# draft10_tofab.net
KiCad netlist of a schematic drawn in EAGLE
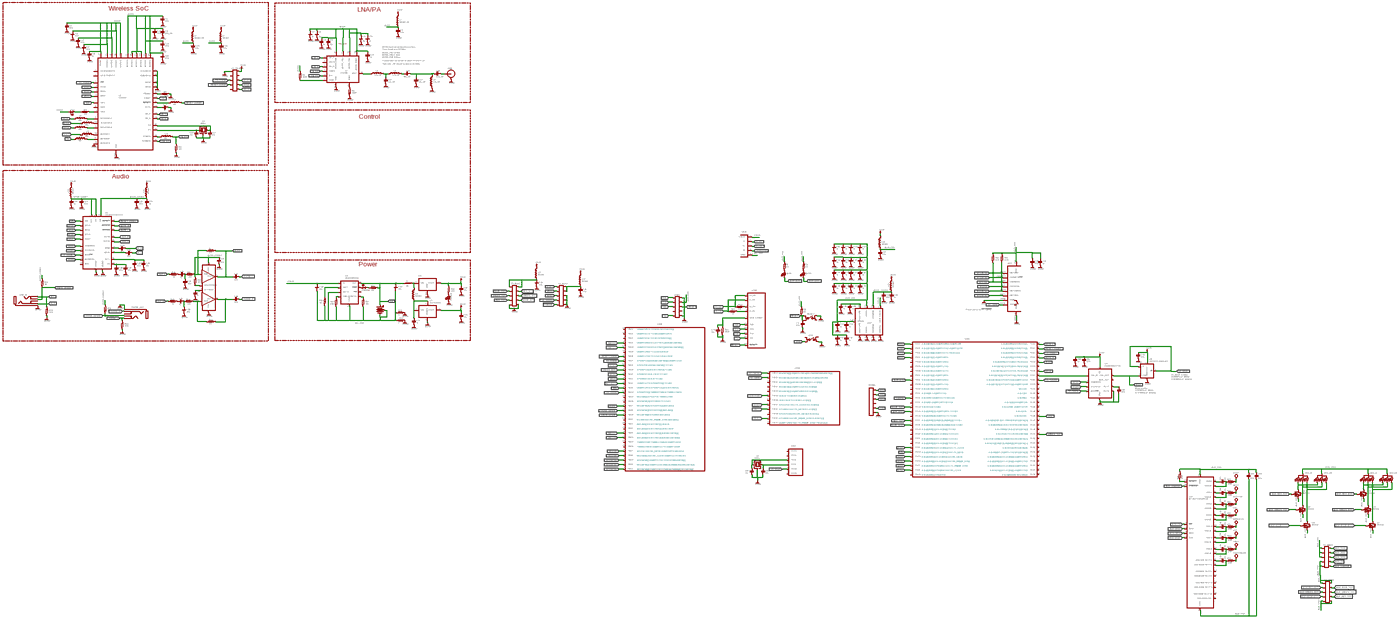
[diagram p0: schematic, sheet 1, overview]
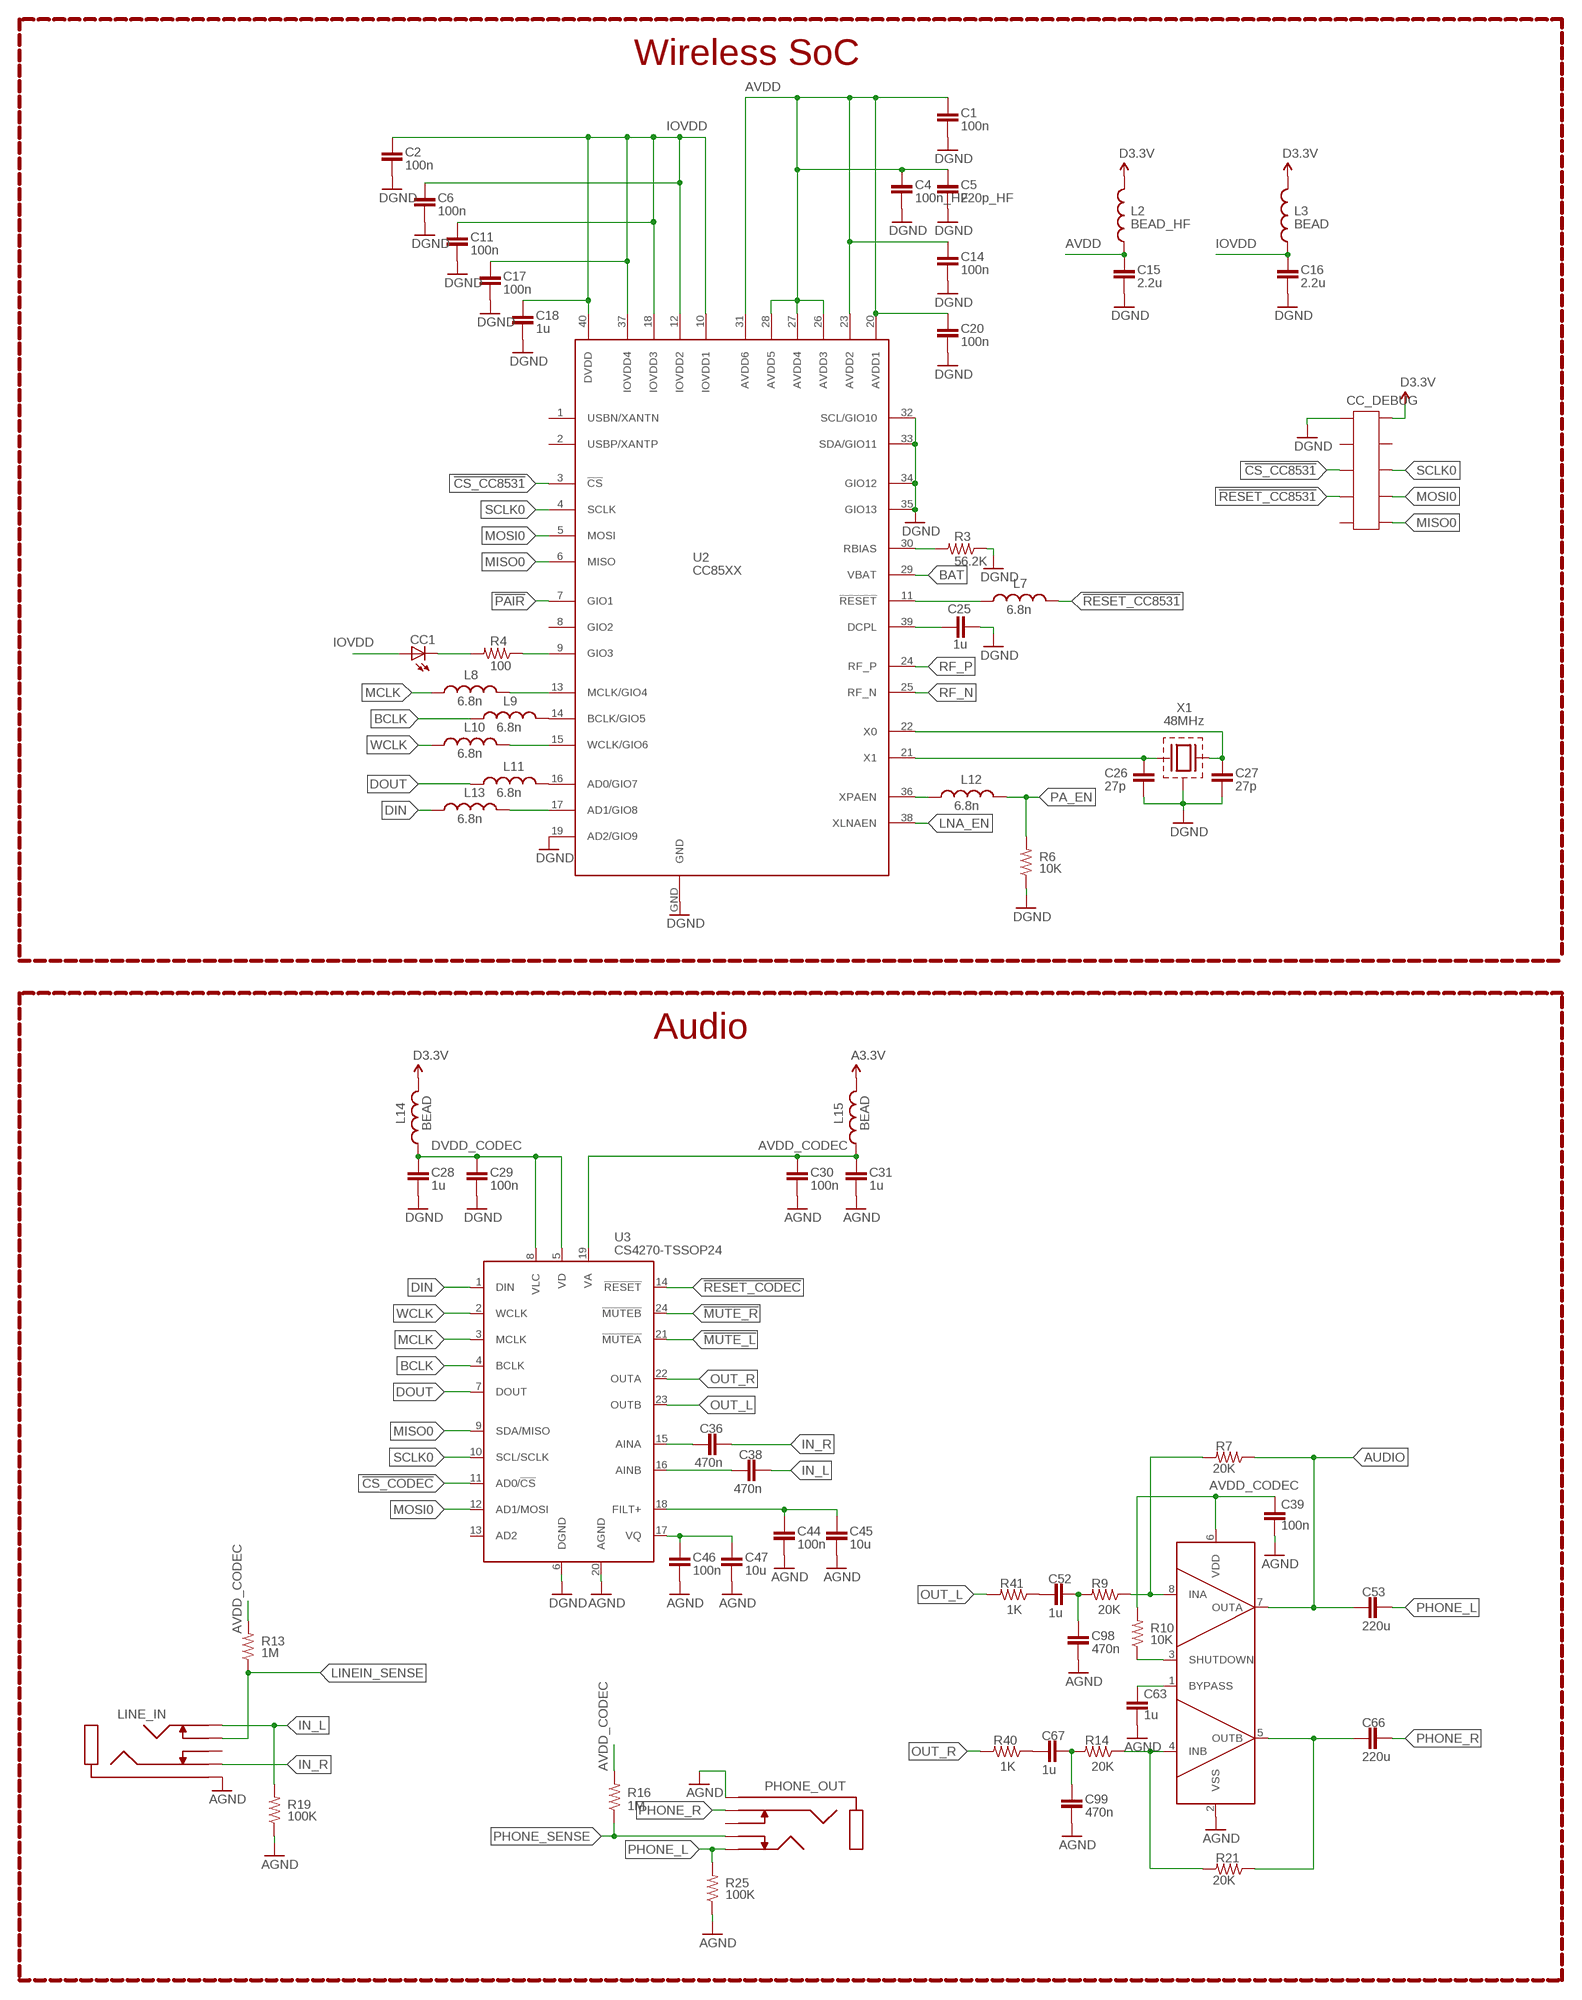
[diagram p1: schematic, sheet 1, part 1 of 4]
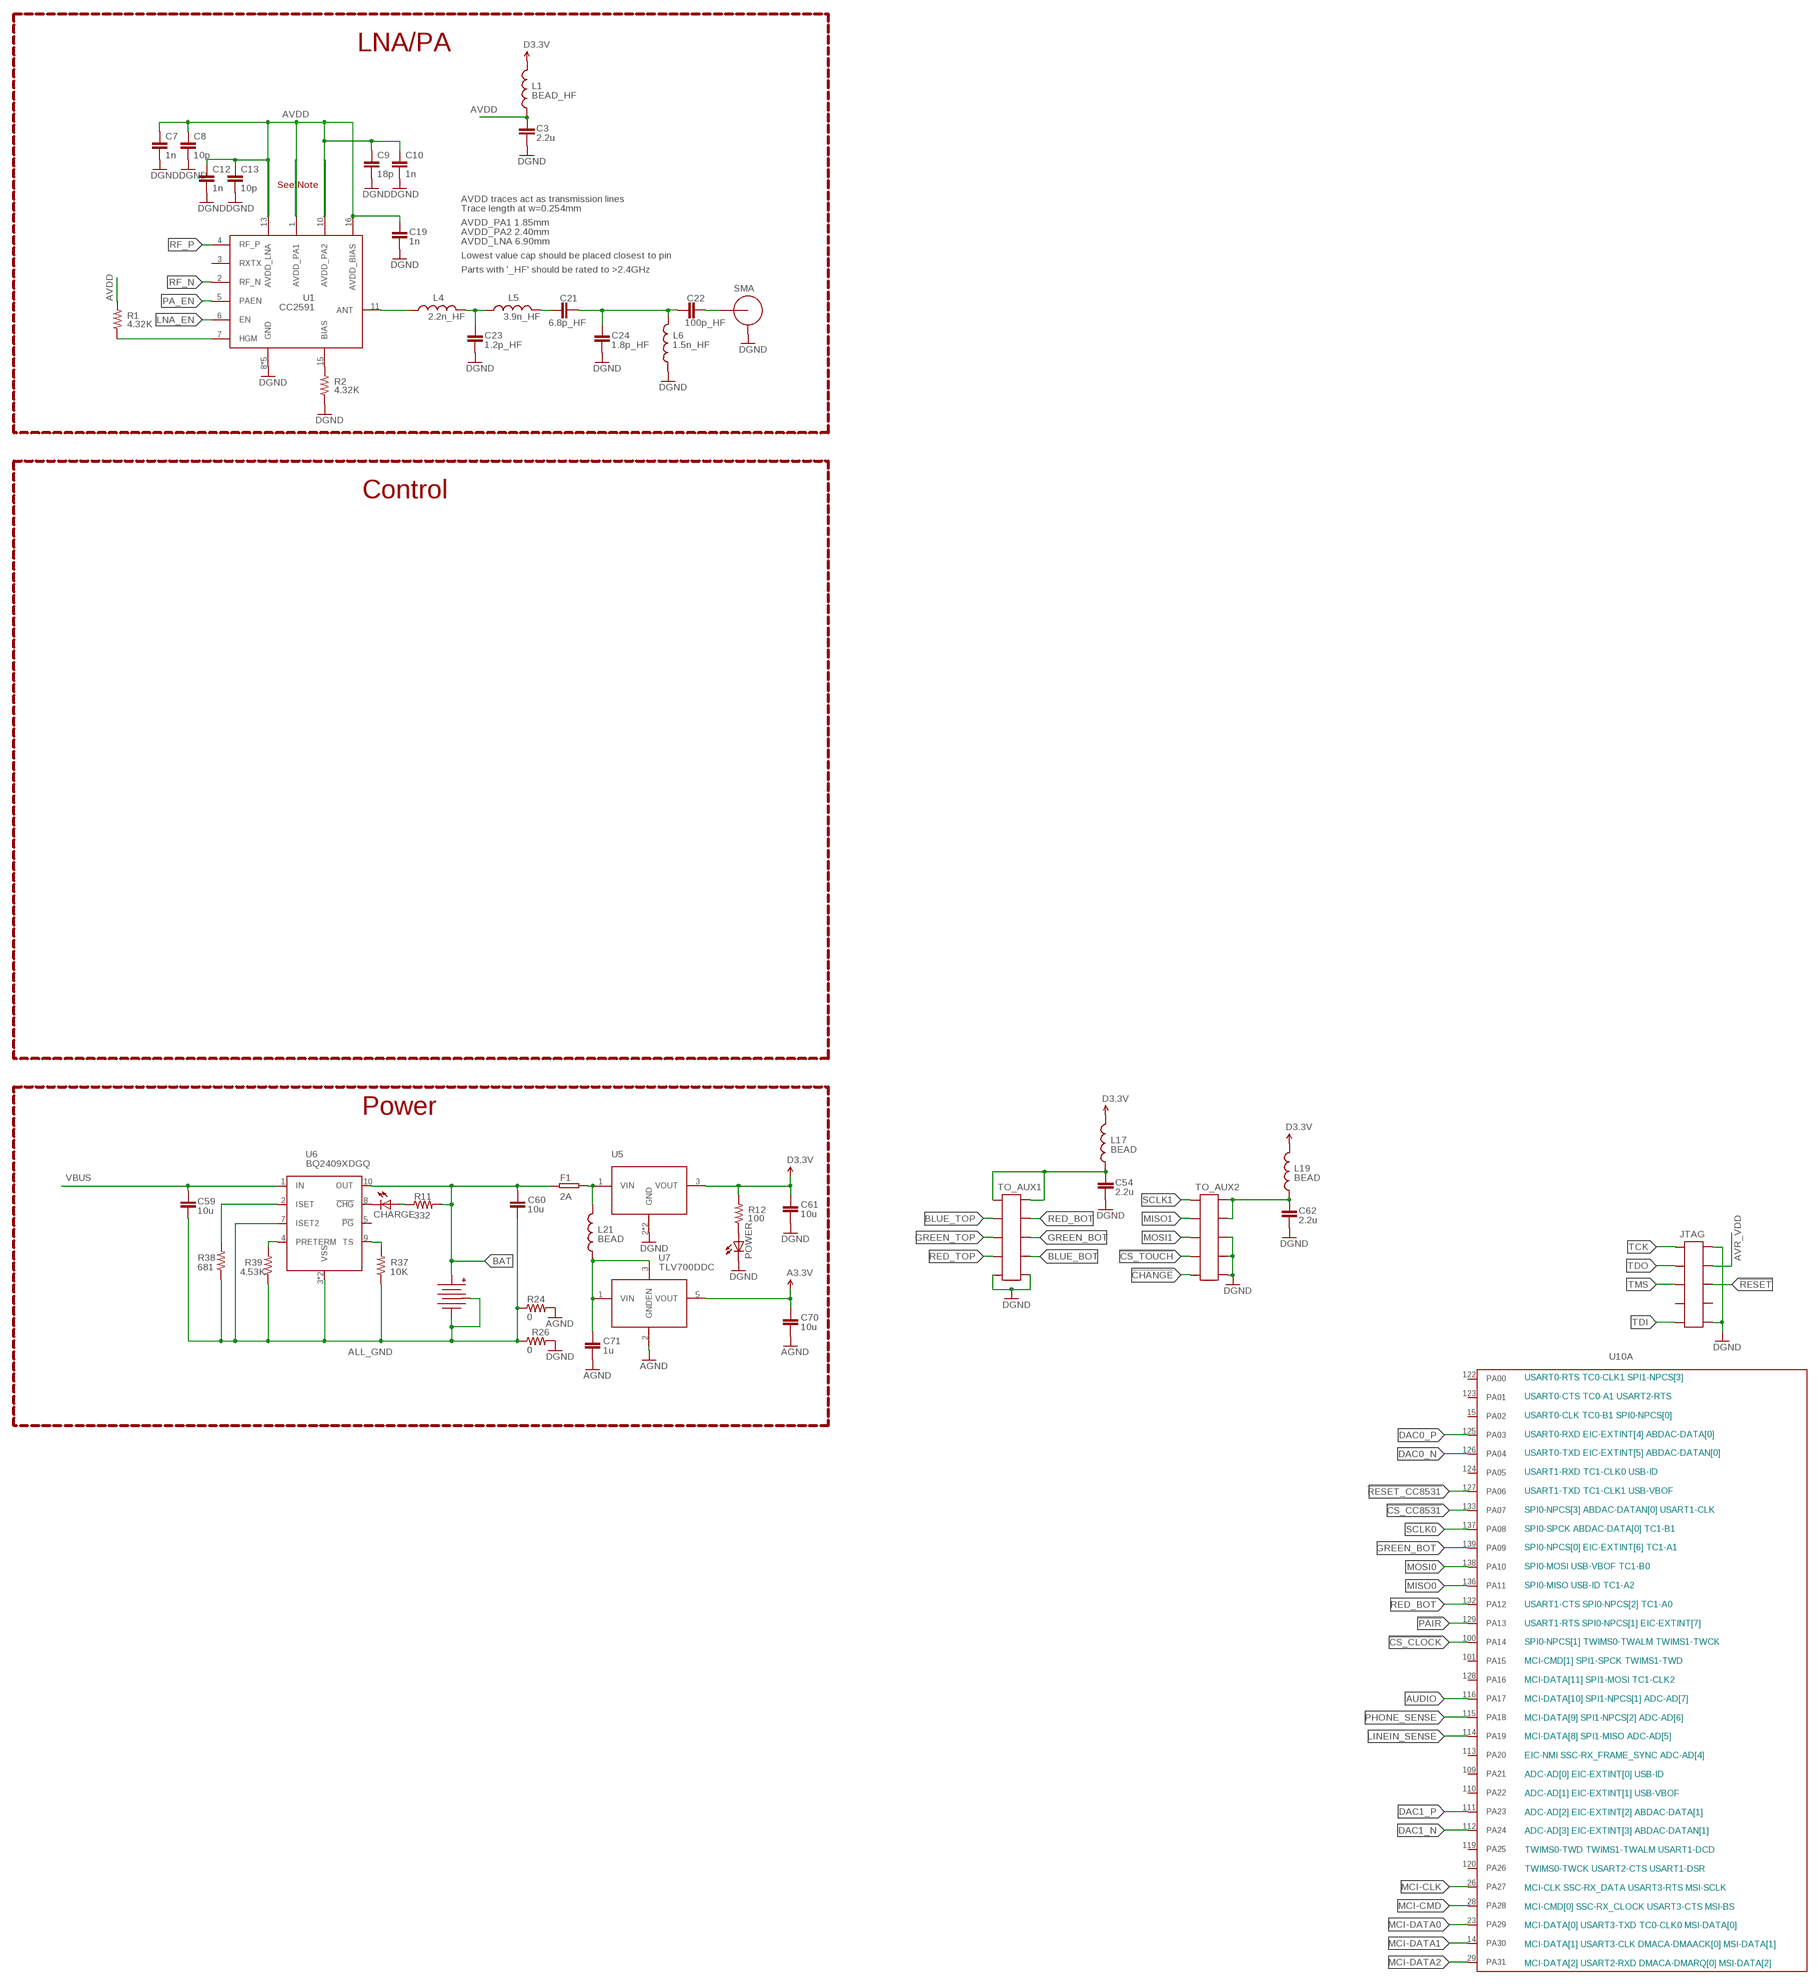
[diagram p2: schematic, sheet 1, part 2 of 4]
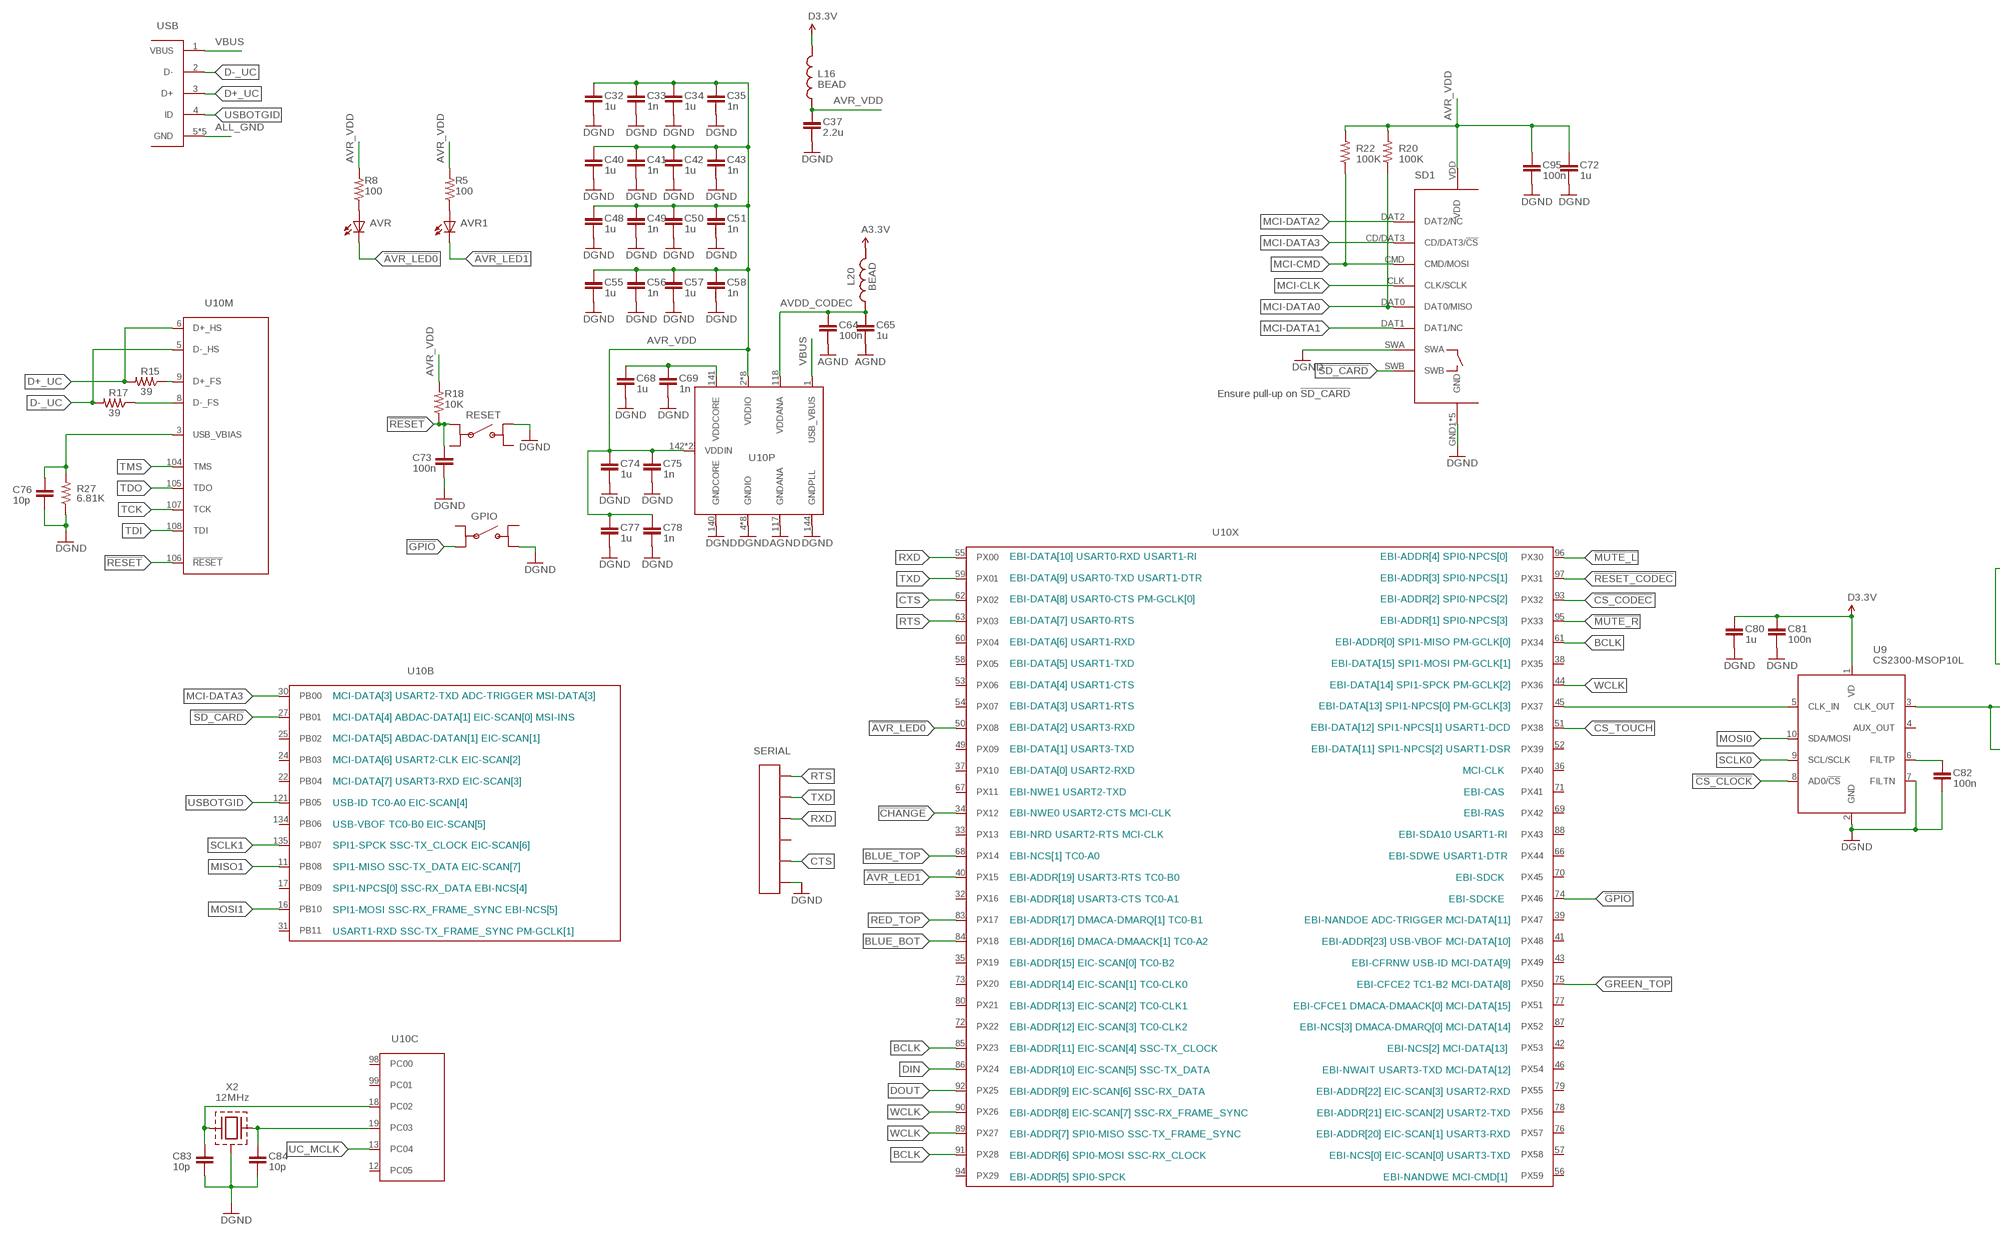
[diagram p3: schematic, sheet 1, part 3 of 4]
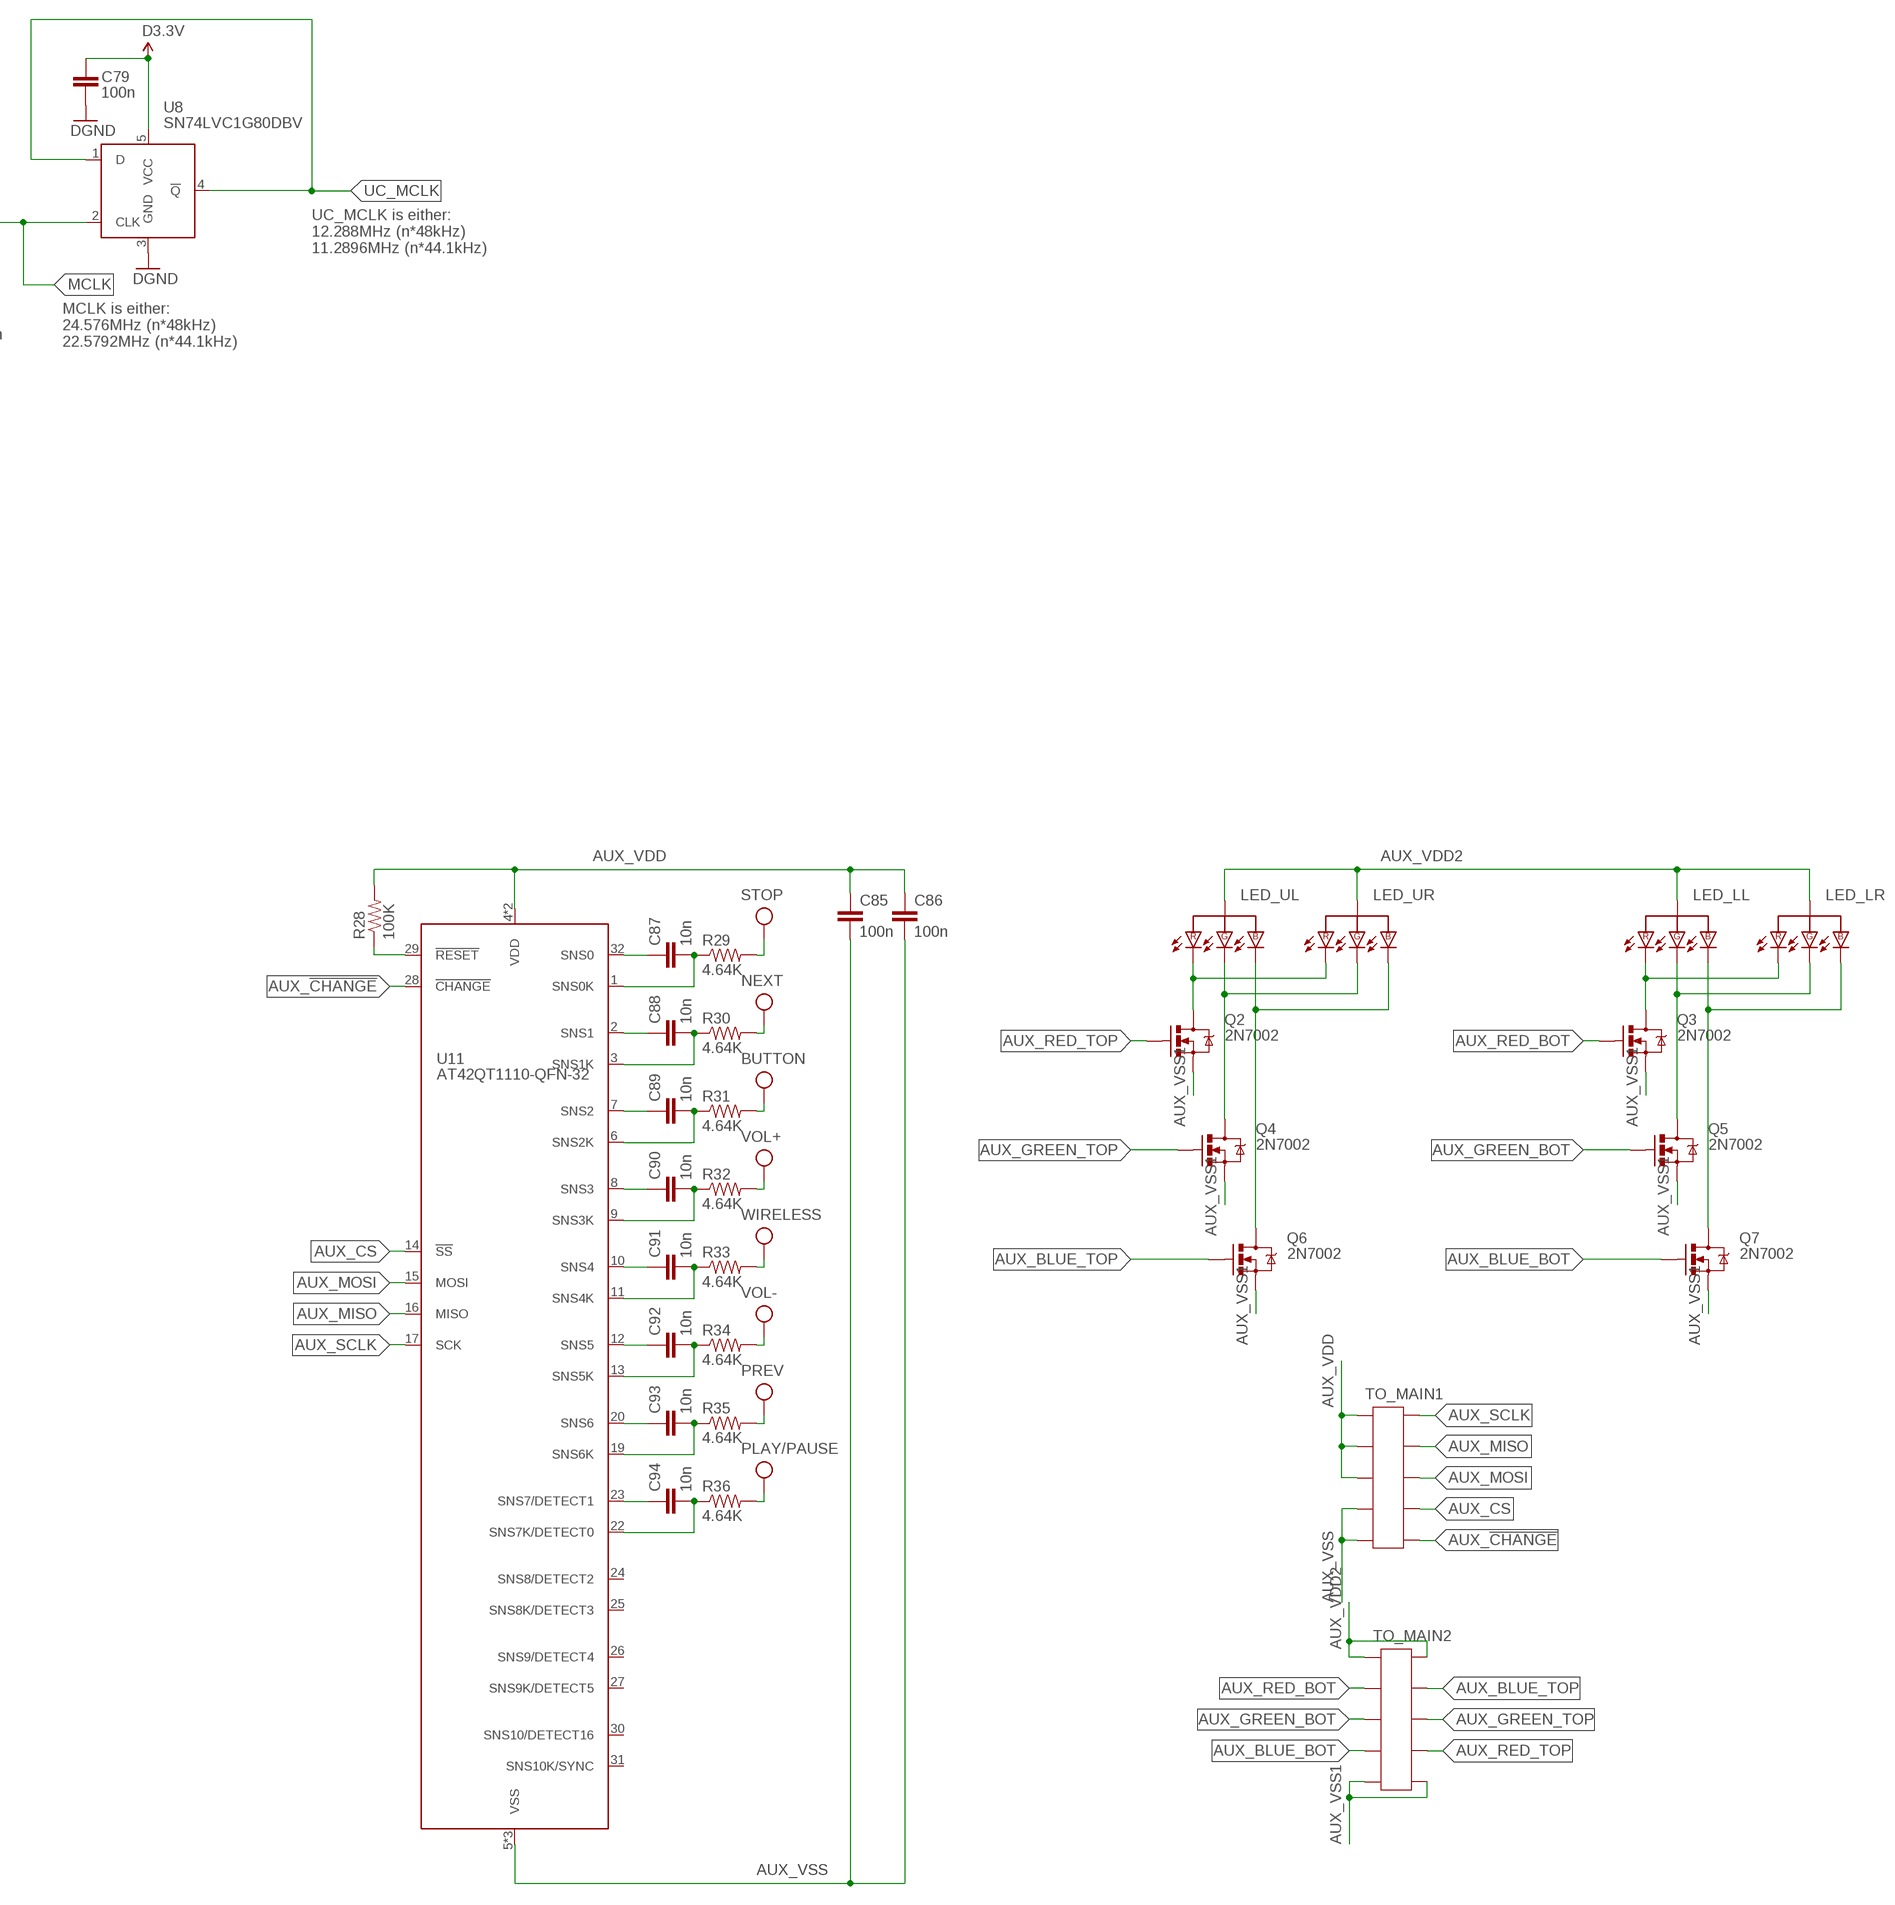
[diagram p4: schematic, sheet 1, part 4 of 4]

(export (version "E")
  (design (tool "Eeschema 10.0.6"))
  (components
    (comp (ref "AVR")
      (value "LED1206")
      (footprint "eagle-import:LED-1206")
      (libsource (lib "eagle-import") (part "LED1206"))
    )
    (comp (ref "AVR1")
      (value "LED1206")
      (footprint "eagle-import:LED-1206")
      (libsource (lib "eagle-import") (part "LED1206"))
    )
    (comp (ref "BATTERY")
      (value "BATTERY-LIPO-JST")
      (footprint "eagle-import:1775469-2")
      (libsource (lib "eagle-import") (part "BATTERY-LIPO-JST"))
    )
    (comp (ref "BUTTON")
      (value "TOUCH_PAD-CIRCLE-10MM")
      (footprint "eagle-import:TOUCH-CIRCLE-10MM")
      (libsource (lib "eagle-import") (part "TOUCH_PAD-CIRCLE-10MM"))
    )
    (comp (ref "C1")
      (value "100n")
      (footprint "eagle-import:C0603")
      (libsource (lib "eagle-import") (part "C-EUC0603"))
    )
    (comp (ref "C2")
      (value "100n")
      (footprint "eagle-import:C0603")
      (libsource (lib "eagle-import") (part "C-EUC0603"))
    )
    (comp (ref "C3")
      (value "2.2u")
      (footprint "eagle-import:C0603")
      (libsource (lib "eagle-import") (part "C-EUC0603"))
    )
    (comp (ref "C4")
      (value "100n_HF")
      (footprint "eagle-import:C0603")
      (libsource (lib "eagle-import") (part "C-EUC0603"))
    )
    (comp (ref "C5")
      (value "220p_HF")
      (footprint "eagle-import:C0603")
      (libsource (lib "eagle-import") (part "C-EUC0603"))
    )
    (comp (ref "C6")
      (value "100n")
      (footprint "eagle-import:C0603")
      (libsource (lib "eagle-import") (part "C-EUC0603"))
    )
    (comp (ref "C7")
      (value "1n")
      (footprint "eagle-import:C0603")
      (libsource (lib "eagle-import") (part "C-EUC0603"))
    )
    (comp (ref "C8")
      (value "10p")
      (footprint "eagle-import:C0603")
      (libsource (lib "eagle-import") (part "C-EUC0603"))
    )
    (comp (ref "C9")
      (value "18p")
      (footprint "eagle-import:C0603")
      (libsource (lib "eagle-import") (part "C-EUC0603"))
    )
    (comp (ref "C10")
      (value "1n")
      (footprint "eagle-import:C0603")
      (libsource (lib "eagle-import") (part "C-EUC0603"))
    )
    (comp (ref "C11")
      (value "100n")
      (footprint "eagle-import:C0603")
      (libsource (lib "eagle-import") (part "C-EUC0603"))
    )
    (comp (ref "C12")
      (value "1n")
      (footprint "eagle-import:C0603")
      (libsource (lib "eagle-import") (part "C-EUC0603"))
    )
    (comp (ref "C13")
      (value "10p")
      (footprint "eagle-import:C0603")
      (libsource (lib "eagle-import") (part "C-EUC0603"))
    )
    (comp (ref "C14")
      (value "100n")
      (footprint "eagle-import:C0603")
      (libsource (lib "eagle-import") (part "C-EUC0603"))
    )
    (comp (ref "C15")
      (value "2.2u")
      (footprint "eagle-import:C0603")
      (libsource (lib "eagle-import") (part "C-EUC0603"))
    )
    (comp (ref "C16")
      (value "2.2u")
      (footprint "eagle-import:C0603")
      (libsource (lib "eagle-import") (part "C-EUC0603"))
    )
    (comp (ref "C17")
      (value "100n")
      (footprint "eagle-import:C0603")
      (libsource (lib "eagle-import") (part "C-EUC0603"))
    )
    (comp (ref "C18")
      (value "1u")
      (footprint "eagle-import:C0603")
      (libsource (lib "eagle-import") (part "C-EUC0603"))
    )
    (comp (ref "C19")
      (value "1n")
      (footprint "eagle-import:C0603")
      (libsource (lib "eagle-import") (part "C-EUC0603"))
    )
    (comp (ref "C20")
      (value "100n")
      (footprint "eagle-import:C0603")
      (libsource (lib "eagle-import") (part "C-EUC0603"))
    )
    (comp (ref "C21")
      (value "6.8p_HF")
      (footprint "eagle-import:C0603")
      (libsource (lib "eagle-import") (part "C-EUC0603"))
    )
    (comp (ref "C22")
      (value "100p_HF")
      (footprint "eagle-import:C0603")
      (libsource (lib "eagle-import") (part "C-EUC0603"))
    )
    (comp (ref "C23")
      (value "1.2p_HF")
      (footprint "eagle-import:C0603")
      (libsource (lib "eagle-import") (part "C-EUC0603"))
    )
    (comp (ref "C24")
      (value "1.8p_HF")
      (footprint "eagle-import:C0603")
      (libsource (lib "eagle-import") (part "C-EUC0603"))
    )
    (comp (ref "C25")
      (value "1u")
      (footprint "eagle-import:C0603")
      (libsource (lib "eagle-import") (part "C-EUC0603"))
    )
    (comp (ref "C26")
      (value "27p")
      (footprint "eagle-import:C0603")
      (libsource (lib "eagle-import") (part "C-EUC0603"))
    )
    (comp (ref "C27")
      (value "27p")
      (footprint "eagle-import:C0603")
      (libsource (lib "eagle-import") (part "C-EUC0603"))
    )
    (comp (ref "C28")
      (value "1u")
      (footprint "eagle-import:C0603")
      (libsource (lib "eagle-import") (part "C-EUC0603"))
    )
    (comp (ref "C29")
      (value "100n")
      (footprint "eagle-import:C0603")
      (libsource (lib "eagle-import") (part "C-EUC0603"))
    )
    (comp (ref "C30")
      (value "100n")
      (footprint "eagle-import:C0603")
      (libsource (lib "eagle-import") (part "C-EUC0603"))
    )
    (comp (ref "C31")
      (value "1u")
      (footprint "eagle-import:C0603")
      (libsource (lib "eagle-import") (part "C-EUC0603"))
    )
    (comp (ref "C32")
      (value "1u")
      (footprint "eagle-import:C0603")
      (libsource (lib "eagle-import") (part "C-EUC0603"))
    )
    (comp (ref "C33")
      (value "1n")
      (footprint "eagle-import:C0603")
      (libsource (lib "eagle-import") (part "C-EUC0603"))
    )
    (comp (ref "C34")
      (value "1u")
      (footprint "eagle-import:C0603")
      (libsource (lib "eagle-import") (part "C-EUC0603"))
    )
    (comp (ref "C35")
      (value "1n")
      (footprint "eagle-import:C0603")
      (libsource (lib "eagle-import") (part "C-EUC0603"))
    )
    (comp (ref "C36")
      (value "470n")
      (footprint "eagle-import:C0603")
      (libsource (lib "eagle-import") (part "C-EUC0603"))
    )
    (comp (ref "C37")
      (value "2.2u")
      (footprint "eagle-import:C0603@1")
      (libsource (lib "eagle-import") (part "rcl_C-EUC0603"))
    )
    (comp (ref "C38")
      (value "470n")
      (footprint "eagle-import:C0603")
      (libsource (lib "eagle-import") (part "C-EUC0603"))
    )
    (comp (ref "C39")
      (value "100n")
      (footprint "eagle-import:C0603")
      (libsource (lib "eagle-import") (part "C-EUC0603"))
    )
    (comp (ref "C40")
      (value "1u")
      (footprint "eagle-import:C0603")
      (libsource (lib "eagle-import") (part "C-EUC0603"))
    )
    (comp (ref "C41")
      (value "1n")
      (footprint "eagle-import:C0603")
      (libsource (lib "eagle-import") (part "C-EUC0603"))
    )
    (comp (ref "C42")
      (value "1u")
      (footprint "eagle-import:C0603")
      (libsource (lib "eagle-import") (part "C-EUC0603"))
    )
    (comp (ref "C43")
      (value "1n")
      (footprint "eagle-import:C0603")
      (libsource (lib "eagle-import") (part "C-EUC0603"))
    )
    (comp (ref "C44")
      (value "100n")
      (footprint "eagle-import:C0603")
      (libsource (lib "eagle-import") (part "C-EUC0603"))
    )
    (comp (ref "C45")
      (value "10u")
      (footprint "eagle-import:C0603")
      (libsource (lib "eagle-import") (part "C-EUC0603"))
    )
    (comp (ref "C46")
      (value "100n")
      (footprint "eagle-import:C0603")
      (libsource (lib "eagle-import") (part "C-EUC0603"))
    )
    (comp (ref "C47")
      (value "10u")
      (footprint "eagle-import:C0603")
      (libsource (lib "eagle-import") (part "C-EUC0603"))
    )
    (comp (ref "C48")
      (value "1u")
      (footprint "eagle-import:C0603")
      (libsource (lib "eagle-import") (part "C-EUC0603"))
    )
    (comp (ref "C49")
      (value "1n")
      (footprint "eagle-import:C0603")
      (libsource (lib "eagle-import") (part "C-EUC0603"))
    )
    (comp (ref "C50")
      (value "1u")
      (footprint "eagle-import:C0603")
      (libsource (lib "eagle-import") (part "C-EUC0603"))
    )
    (comp (ref "C51")
      (value "1n")
      (footprint "eagle-import:C0603")
      (libsource (lib "eagle-import") (part "C-EUC0603"))
    )
    (comp (ref "C52")
      (value "1u")
      (footprint "eagle-import:C0603")
      (libsource (lib "eagle-import") (part "C-EUC0603"))
    )
    (comp (ref "C53")
      (value "220u")
      (footprint "eagle-import:C1210")
      (libsource (lib "eagle-import") (part "C-EUC1210"))
    )
    (comp (ref "C54")
      (value "2.2u")
      (footprint "eagle-import:C0603")
      (libsource (lib "eagle-import") (part "C-EUC0603"))
    )
    (comp (ref "C55")
      (value "1u")
      (footprint "eagle-import:C0603")
      (libsource (lib "eagle-import") (part "C-EUC0603"))
    )
    (comp (ref "C56")
      (value "1n")
      (footprint "eagle-import:C0603")
      (libsource (lib "eagle-import") (part "C-EUC0603"))
    )
    (comp (ref "C57")
      (value "1u")
      (footprint "eagle-import:C0603")
      (libsource (lib "eagle-import") (part "C-EUC0603"))
    )
    (comp (ref "C58")
      (value "1n")
      (footprint "eagle-import:C0603")
      (libsource (lib "eagle-import") (part "C-EUC0603"))
    )
    (comp (ref "C59")
      (value "10u")
      (footprint "eagle-import:C0603")
      (libsource (lib "eagle-import") (part "C-EUC0603"))
    )
    (comp (ref "C60")
      (value "10u")
      (footprint "eagle-import:C0603")
      (libsource (lib "eagle-import") (part "C-EUC0603"))
    )
    (comp (ref "C61")
      (value "10u")
      (footprint "eagle-import:C0603")
      (libsource (lib "eagle-import") (part "C-EUC0603"))
    )
    (comp (ref "C62")
      (value "2.2u")
      (footprint "eagle-import:C0603")
      (libsource (lib "eagle-import") (part "C-EUC0603"))
    )
    (comp (ref "C63")
      (value "1u")
      (footprint "eagle-import:C0603")
      (libsource (lib "eagle-import") (part "C-EUC0603"))
    )
    (comp (ref "C64")
      (value "100n")
      (footprint "eagle-import:C0603")
      (libsource (lib "eagle-import") (part "C-EUC0603"))
    )
    (comp (ref "C65")
      (value "1u")
      (footprint "eagle-import:C0603")
      (libsource (lib "eagle-import") (part "C-EUC0603"))
    )
    (comp (ref "C66")
      (value "220u")
      (footprint "eagle-import:C1210")
      (libsource (lib "eagle-import") (part "C-EUC1210"))
    )
    (comp (ref "C67")
      (value "1u")
      (footprint "eagle-import:C0603")
      (libsource (lib "eagle-import") (part "C-EUC0603"))
    )
    (comp (ref "C68")
      (value "1u")
      (footprint "eagle-import:C0603")
      (libsource (lib "eagle-import") (part "C-EUC0603"))
    )
    (comp (ref "C69")
      (value "1n")
      (footprint "eagle-import:C0603")
      (libsource (lib "eagle-import") (part "C-EUC0603"))
    )
    (comp (ref "C70")
      (value "10u")
      (footprint "eagle-import:C0603@1")
      (libsource (lib "eagle-import") (part "rcl_C-EUC0603"))
    )
    (comp (ref "C71")
      (value "1u")
      (footprint "eagle-import:C0603")
      (libsource (lib "eagle-import") (part "C-EUC0603"))
    )
    (comp (ref "C72")
      (value "1u")
      (footprint "eagle-import:C0603")
      (libsource (lib "eagle-import") (part "C-EUC0603"))
    )
    (comp (ref "C73")
      (value "100n")
      (footprint "eagle-import:C0603")
      (libsource (lib "eagle-import") (part "C-EUC0603"))
    )
    (comp (ref "C74")
      (value "1u")
      (footprint "eagle-import:C0603")
      (libsource (lib "eagle-import") (part "C-EUC0603"))
    )
    (comp (ref "C75")
      (value "1n")
      (footprint "eagle-import:C0603")
      (libsource (lib "eagle-import") (part "C-EUC0603"))
    )
    (comp (ref "C76")
      (value "10p")
      (footprint "eagle-import:C0603")
      (libsource (lib "eagle-import") (part "C-EUC0603"))
    )
    (comp (ref "C77")
      (value "1u")
      (footprint "eagle-import:C0603")
      (libsource (lib "eagle-import") (part "C-EUC0603"))
    )
    (comp (ref "C78")
      (value "1n")
      (footprint "eagle-import:C0603")
      (libsource (lib "eagle-import") (part "C-EUC0603"))
    )
    (comp (ref "C79")
      (value "100n")
      (footprint "eagle-import:C0603")
      (libsource (lib "eagle-import") (part "C-EUC0603"))
    )
    (comp (ref "C80")
      (value "1u")
      (footprint "eagle-import:C0603")
      (libsource (lib "eagle-import") (part "C-EUC0603"))
    )
    (comp (ref "C81")
      (value "100n")
      (footprint "eagle-import:C0603")
      (libsource (lib "eagle-import") (part "C-EUC0603"))
    )
    (comp (ref "C82")
      (value "100n")
      (footprint "eagle-import:C0603")
      (libsource (lib "eagle-import") (part "C-EUC0603"))
    )
    (comp (ref "C83")
      (value "10p")
      (footprint "eagle-import:C0603")
      (libsource (lib "eagle-import") (part "C-EUC0603"))
    )
    (comp (ref "C84")
      (value "10p")
      (footprint "eagle-import:C0603")
      (libsource (lib "eagle-import") (part "C-EUC0603"))
    )
    (comp (ref "C85")
      (value "100n")
      (footprint "eagle-import:C0603")
      (libsource (lib "eagle-import") (part "C-EUC0603"))
    )
    (comp (ref "C86")
      (value "100n")
      (footprint "eagle-import:C0603")
      (libsource (lib "eagle-import") (part "C-EUC0603"))
    )
    (comp (ref "C87")
      (value "10n")
      (footprint "eagle-import:C0603")
      (libsource (lib "eagle-import") (part "C-EUC0603"))
    )
    (comp (ref "C88")
      (value "10n")
      (footprint "eagle-import:C0603")
      (libsource (lib "eagle-import") (part "C-EUC0603"))
    )
    (comp (ref "C89")
      (value "10n")
      (footprint "eagle-import:C0603")
      (libsource (lib "eagle-import") (part "C-EUC0603"))
    )
    (comp (ref "C90")
      (value "10n")
      (footprint "eagle-import:C0603")
      (libsource (lib "eagle-import") (part "C-EUC0603"))
    )
    (comp (ref "C91")
      (value "10n")
      (footprint "eagle-import:C0603")
      (libsource (lib "eagle-import") (part "C-EUC0603"))
    )
    (comp (ref "C92")
      (value "10n")
      (footprint "eagle-import:C0603")
      (libsource (lib "eagle-import") (part "C-EUC0603"))
    )
    (comp (ref "C93")
      (value "10n")
      (footprint "eagle-import:C0603")
      (libsource (lib "eagle-import") (part "C-EUC0603"))
    )
    (comp (ref "C94")
      (value "10n")
      (footprint "eagle-import:C0603")
      (libsource (lib "eagle-import") (part "C-EUC0603"))
    )
    (comp (ref "C95")
      (value "100n")
      (footprint "eagle-import:C0603")
      (libsource (lib "eagle-import") (part "C-EUC0603"))
    )
    (comp (ref "C98")
      (value "470n")
      (footprint "eagle-import:C0603")
      (libsource (lib "eagle-import") (part "C-EUC0603"))
    )
    (comp (ref "C99")
      (value "470n")
      (footprint "eagle-import:C0603")
      (libsource (lib "eagle-import") (part "C-EUC0603"))
    )
    (comp (ref "CC1")
      (value "LED1206")
      (footprint "eagle-import:LED-1206")
      (libsource (lib "eagle-import") (part "LED1206"))
    )
    (comp (ref "CC_DEBUG")
      (value "HEADER-10P-SMD-MALE2")
      (footprint "eagle-import:HEADER-10P-1.27MM")
      (libsource (lib "eagle-import") (part "HEADER-10P-SMD-MALE2"))
    )
    (comp (ref "CHARGE")
      (value "LED1206")
      (footprint "eagle-import:LED-1206")
      (libsource (lib "eagle-import") (part "LED1206"))
    )
    (comp (ref "F1")
      (value "2A")
      (footprint "eagle-import:1210")
      (libsource (lib "eagle-import") (part "PTC_FUSE"))
    )
    (comp (ref "GPIO")
      (value "TACT_SWITCH-PTS-525")
      (footprint "eagle-import:PTS-525")
      (libsource (lib "eagle-import") (part "TACT_SWITCH-PTS-525"))
    )
    (comp (ref "JTAG")
      (value "HEADER-10P-SMD-MALE2")
      (footprint "eagle-import:HEADER-10P-1.27MM")
      (libsource (lib "eagle-import") (part "HEADER-10P-SMD-MALE2"))
    )
    (comp (ref "L1")
      (value "BEAD_HF")
      (footprint "eagle-import:0603")
      (libsource (lib "eagle-import") (part "INDUCTOR0603"))
    )
    (comp (ref "L2")
      (value "BEAD_HF")
      (footprint "eagle-import:0603")
      (libsource (lib "eagle-import") (part "INDUCTOR0603"))
    )
    (comp (ref "L3")
      (value "BEAD")
      (footprint "eagle-import:0603")
      (libsource (lib "eagle-import") (part "INDUCTOR0603"))
    )
    (comp (ref "L4")
      (value "2.2n_HF")
      (footprint "eagle-import:0603")
      (libsource (lib "eagle-import") (part "INDUCTOR0603"))
    )
    (comp (ref "L5")
      (value "3.9n_HF")
      (footprint "eagle-import:0603")
      (libsource (lib "eagle-import") (part "INDUCTOR0603"))
    )
    (comp (ref "L6")
      (value "1.5n_HF")
      (footprint "eagle-import:0603")
      (libsource (lib "eagle-import") (part "INDUCTOR0603"))
    )
    (comp (ref "L7")
      (value "6.8n")
      (footprint "eagle-import:0603")
      (libsource (lib "eagle-import") (part "INDUCTOR0603"))
    )
    (comp (ref "L8")
      (value "6.8n")
      (footprint "eagle-import:0603")
      (libsource (lib "eagle-import") (part "INDUCTOR0603"))
    )
    (comp (ref "L9")
      (value "6.8n")
      (footprint "eagle-import:0603")
      (libsource (lib "eagle-import") (part "INDUCTOR0603"))
    )
    (comp (ref "L10")
      (value "6.8n")
      (footprint "eagle-import:0603")
      (libsource (lib "eagle-import") (part "INDUCTOR0603"))
    )
    (comp (ref "L11")
      (value "6.8n")
      (footprint "eagle-import:0603")
      (libsource (lib "eagle-import") (part "INDUCTOR0603"))
    )
    (comp (ref "L12")
      (value "6.8n")
      (footprint "eagle-import:0603@1")
      (libsource (lib "eagle-import") (part "SparkFun-Passives_INDUCTOR0603"))
    )
    (comp (ref "L13")
      (value "6.8n")
      (footprint "eagle-import:0603")
      (libsource (lib "eagle-import") (part "INDUCTOR0603"))
    )
    (comp (ref "L14")
      (value "BEAD")
      (footprint "eagle-import:0603")
      (libsource (lib "eagle-import") (part "INDUCTOR0603"))
    )
    (comp (ref "L15")
      (value "BEAD")
      (footprint "eagle-import:0603@1")
      (libsource (lib "eagle-import") (part "SparkFun-Passives_INDUCTOR0603"))
    )
    (comp (ref "L16")
      (value "BEAD")
      (footprint "eagle-import:0603@1")
      (libsource (lib "eagle-import") (part "SparkFun-Passives_INDUCTOR0603"))
    )
    (comp (ref "L17")
      (value "BEAD")
      (footprint "eagle-import:0603")
      (libsource (lib "eagle-import") (part "INDUCTOR0603"))
    )
    (comp (ref "L19")
      (value "BEAD")
      (footprint "eagle-import:0603")
      (libsource (lib "eagle-import") (part "INDUCTOR0603"))
    )
    (comp (ref "L20")
      (value "BEAD")
      (footprint "eagle-import:0603")
      (libsource (lib "eagle-import") (part "INDUCTOR0603"))
    )
    (comp (ref "L21")
      (value "BEAD")
      (footprint "eagle-import:0603")
      (libsource (lib "eagle-import") (part "INDUCTOR0603"))
    )
    (comp (ref "LED_LL")
      (value "LED_RGB")
      (footprint "eagle-import:PLCC-4")
      (libsource (lib "eagle-import") (part "LED_RGB"))
    )
    (comp (ref "LED_LR")
      (value "LED_RGB")
      (footprint "eagle-import:PLCC-4")
      (libsource (lib "eagle-import") (part "LED_RGB"))
    )
    (comp (ref "LED_UL")
      (value "LED_RGB")
      (footprint "eagle-import:PLCC-4")
      (libsource (lib "eagle-import") (part "LED_RGB"))
    )
    (comp (ref "LED_UR")
      (value "LED_RGB")
      (footprint "eagle-import:PLCC-4")
      (libsource (lib "eagle-import") (part "LED_RGB"))
    )
    (comp (ref "LINE_IN")
      (value "PHONE_SW-STX-35332-5N")
      (footprint "eagle-import:STX-35332-5N")
      (libsource (lib "eagle-import") (part "PHONE_SW-STX-35332-5N"))
    )
    (comp (ref "NEXT")
      (value "TOUCH_PAD-CIRCLE-10MM")
      (footprint "eagle-import:TOUCH-CIRCLE-10MM")
      (libsource (lib "eagle-import") (part "TOUCH_PAD-CIRCLE-10MM"))
    )
    (comp (ref "PHONE_OUT")
      (value "PHONE_SW-STX-35332-5N")
      (footprint "eagle-import:STX-35332-5N")
      (libsource (lib "eagle-import") (part "PHONE_SW-STX-35332-5N"))
    )
    (comp (ref "PLAY/PAUSE")
      (value "TOUCH_PAD-CIRCLE-10MM")
      (footprint "eagle-import:TOUCH-CIRCLE-10MM")
      (libsource (lib "eagle-import") (part "TOUCH_PAD-CIRCLE-10MM"))
    )
    (comp (ref "POWER")
      (value "LED1206")
      (footprint "eagle-import:LED-1206")
      (libsource (lib "eagle-import") (part "LED1206"))
    )
    (comp (ref "PREV")
      (value "TOUCH_PAD-CIRCLE-10MM")
      (footprint "eagle-import:TOUCH-CIRCLE-10MM")
      (libsource (lib "eagle-import") (part "TOUCH_PAD-CIRCLE-10MM"))
    )
    (comp (ref "Q2")
      (value "2N7002")
      (footprint "eagle-import:SOT23-3")
      (libsource (lib "eagle-import") (part "MOSFET-NCHANNELSMD"))
    )
    (comp (ref "Q3")
      (value "2N7002")
      (footprint "eagle-import:SOT23-3")
      (libsource (lib "eagle-import") (part "MOSFET-NCHANNELSMD"))
    )
    (comp (ref "Q4")
      (value "2N7002")
      (footprint "eagle-import:SOT23-3")
      (libsource (lib "eagle-import") (part "MOSFET-NCHANNELSMD"))
    )
    (comp (ref "Q5")
      (value "2N7002")
      (footprint "eagle-import:SOT23-3")
      (libsource (lib "eagle-import") (part "MOSFET-NCHANNELSMD"))
    )
    (comp (ref "Q6")
      (value "2N7002")
      (footprint "eagle-import:SOT23-3")
      (libsource (lib "eagle-import") (part "MOSFET-NCHANNELSMD"))
    )
    (comp (ref "Q7")
      (value "2N7002")
      (footprint "eagle-import:SOT23-3")
      (libsource (lib "eagle-import") (part "MOSFET-NCHANNELSMD"))
    )
    (comp (ref "R1")
      (value "4.32K")
      (footprint "eagle-import:R0603")
      (libsource (lib "eagle-import") (part "R-US_R0603"))
    )
    (comp (ref "R2")
      (value "4.32K")
      (footprint "eagle-import:R0603")
      (libsource (lib "eagle-import") (part "R-US_R0603"))
    )
    (comp (ref "R3")
      (value "56.2K")
      (footprint "eagle-import:R0603")
      (libsource (lib "eagle-import") (part "R-US_R0603"))
    )
    (comp (ref "R4")
      (value "100")
      (footprint "eagle-import:R0603")
      (libsource (lib "eagle-import") (part "R-US_R0603"))
    )
    (comp (ref "R5")
      (value "100")
      (footprint "eagle-import:R0603")
      (libsource (lib "eagle-import") (part "R-US_R0603"))
    )
    (comp (ref "R6")
      (value "10K")
      (footprint "eagle-import:R0603")
      (libsource (lib "eagle-import") (part "R-US_R0603"))
    )
    (comp (ref "R7")
      (value "20K")
      (footprint "eagle-import:R0603")
      (libsource (lib "eagle-import") (part "R-US_R0603"))
    )
    (comp (ref "R8")
      (value "100")
      (footprint "eagle-import:R0603")
      (libsource (lib "eagle-import") (part "R-US_R0603"))
    )
    (comp (ref "R9")
      (value "20K")
      (footprint "eagle-import:R0603")
      (libsource (lib "eagle-import") (part "R-US_R0603"))
    )
    (comp (ref "R10")
      (value "10K")
      (footprint "eagle-import:R0603@1")
      (libsource (lib "eagle-import") (part "rcl_R-US_R0603"))
    )
    (comp (ref "R11")
      (value "332")
      (footprint "eagle-import:R0603")
      (libsource (lib "eagle-import") (part "R-US_R0603"))
    )
    (comp (ref "R12")
      (value "100")
      (footprint "eagle-import:R0603")
      (libsource (lib "eagle-import") (part "R-US_R0603"))
    )
    (comp (ref "R13")
      (value "1M")
      (footprint "eagle-import:R0603")
      (libsource (lib "eagle-import") (part "R-US_R0603"))
    )
    (comp (ref "R14")
      (value "20K")
      (footprint "eagle-import:R0603")
      (libsource (lib "eagle-import") (part "R-US_R0603"))
    )
    (comp (ref "R15")
      (value "39")
      (footprint "eagle-import:R0603")
      (libsource (lib "eagle-import") (part "R-US_R0603"))
    )
    (comp (ref "R16")
      (value "1M")
      (footprint "eagle-import:R0603")
      (libsource (lib "eagle-import") (part "R-US_R0603"))
    )
    (comp (ref "R17")
      (value "39")
      (footprint "eagle-import:R0603")
      (libsource (lib "eagle-import") (part "R-US_R0603"))
    )
    (comp (ref "R18")
      (value "10K")
      (footprint "eagle-import:R0603")
      (libsource (lib "eagle-import") (part "R-US_R0603"))
    )
    (comp (ref "R19")
      (value "100K")
      (footprint "eagle-import:R0603")
      (libsource (lib "eagle-import") (part "R-US_R0603"))
    )
    (comp (ref "R20")
      (value "100K")
      (footprint "eagle-import:R0603")
      (libsource (lib "eagle-import") (part "R-US_R0603"))
    )
    (comp (ref "R21")
      (value "20K")
      (footprint "eagle-import:R0603")
      (libsource (lib "eagle-import") (part "R-US_R0603"))
    )
    (comp (ref "R22")
      (value "100K")
      (footprint "eagle-import:R0603")
      (libsource (lib "eagle-import") (part "R-US_R0603"))
    )
    (comp (ref "R24")
      (value "0")
      (footprint "eagle-import:R0603")
      (libsource (lib "eagle-import") (part "R-US_R0603"))
    )
    (comp (ref "R25")
      (value "100K")
      (footprint "eagle-import:R0603")
      (libsource (lib "eagle-import") (part "R-US_R0603"))
    )
    (comp (ref "R26")
      (value "0")
      (footprint "eagle-import:R0603")
      (libsource (lib "eagle-import") (part "R-US_R0603"))
    )
    (comp (ref "R27")
      (value "6.81K")
      (footprint "eagle-import:R0603")
      (libsource (lib "eagle-import") (part "R-US_R0603"))
    )
    (comp (ref "R28")
      (value "100K")
      (footprint "eagle-import:R0603")
      (libsource (lib "eagle-import") (part "R-US_R0603"))
    )
    (comp (ref "R29")
      (value "4.64K")
      (footprint "eagle-import:R0603")
      (libsource (lib "eagle-import") (part "R-US_R0603"))
    )
    (comp (ref "R30")
      (value "4.64K")
      (footprint "eagle-import:R0603")
      (libsource (lib "eagle-import") (part "R-US_R0603"))
    )
    (comp (ref "R31")
      (value "4.64K")
      (footprint "eagle-import:R0603")
      (libsource (lib "eagle-import") (part "R-US_R0603"))
    )
    (comp (ref "R32")
      (value "4.64K")
      (footprint "eagle-import:R0603")
      (libsource (lib "eagle-import") (part "R-US_R0603"))
    )
    (comp (ref "R33")
      (value "4.64K")
      (footprint "eagle-import:R0603")
      (libsource (lib "eagle-import") (part "R-US_R0603"))
    )
    (comp (ref "R34")
      (value "4.64K")
      (footprint "eagle-import:R0603")
      (libsource (lib "eagle-import") (part "R-US_R0603"))
    )
    (comp (ref "R35")
      (value "4.64K")
      (footprint "eagle-import:R0603")
      (libsource (lib "eagle-import") (part "R-US_R0603"))
    )
    (comp (ref "R36")
      (value "4.64K")
      (footprint "eagle-import:R0603")
      (libsource (lib "eagle-import") (part "R-US_R0603"))
    )
    (comp (ref "R37")
      (value "10K")
      (footprint "eagle-import:R0603")
      (libsource (lib "eagle-import") (part "R-US_R0603"))
    )
    (comp (ref "R38")
      (value "681")
      (footprint "eagle-import:R0603")
      (libsource (lib "eagle-import") (part "R-US_R0603"))
    )
    (comp (ref "R39")
      (value "4.53K")
      (footprint "eagle-import:R0603")
      (libsource (lib "eagle-import") (part "R-US_R0603"))
    )
    (comp (ref "R40")
      (value "1K")
      (footprint "eagle-import:R0603")
      (libsource (lib "eagle-import") (part "R-US_R0603"))
    )
    (comp (ref "R41")
      (value "1K")
      (footprint "eagle-import:R0603")
      (libsource (lib "eagle-import") (part "R-US_R0603"))
    )
    (comp (ref "RESET")
      (value "TACT_SWITCH-PTS-525")
      (footprint "eagle-import:PTS-525")
      (libsource (lib "eagle-import") (part "TACT_SWITCH-PTS-525"))
    )
    (comp (ref "SD1")
      (value "MICROSD104031-0811")
      (footprint "eagle-import:MOLEX_104031-0811")
      (libsource (lib "eagle-import") (part "MICROSD104031-0811"))
    )
    (comp (ref "SERIAL")
      (value "HEADER-6X1-961106-5500")
      (footprint "eagle-import:HEADER-3M-961-6P-2.54MM")
      (libsource (lib "eagle-import") (part "HEADER-6X1-961106-5500"))
    )
    (comp (ref "SMA")
      (value "SMA-REVSMA-0.62")
      (footprint "eagle-import:CONREVSMA003.062")
      (libsource (lib "eagle-import") (part "SMA-REVSMA-0.62"))
    )
    (comp (ref "STOP")
      (value "TOUCH_PAD-CIRCLE-10MM")
      (footprint "eagle-import:TOUCH-CIRCLE-10MM")
      (libsource (lib "eagle-import") (part "TOUCH_PAD-CIRCLE-10MM"))
    )
    (comp (ref "TO_AUX1")
      (value "HEADER-10P-SMD-2MM-FEMALE")
      (footprint "eagle-import:M22-63405")
      (libsource (lib "eagle-import") (part "HEADER-10P-SMD-2MM-FEMALE"))
    )
    (comp (ref "TO_AUX2")
      (value "HEADER-10P-SMD-2MM-FEMALE")
      (footprint "eagle-import:M22-63405")
      (libsource (lib "eagle-import") (part "HEADER-10P-SMD-2MM-FEMALE"))
    )
    (comp (ref "TO_MAIN1")
      (value "HEADER-10P-SMD-2MM-MALE")
      (footprint "eagle-import:M22-53205")
      (libsource (lib "eagle-import") (part "HEADER-10P-SMD-2MM-MALE"))
    )
    (comp (ref "TO_MAIN2")
      (value "HEADER-10P-SMD-2MM-MALE")
      (footprint "eagle-import:M22-53205")
      (libsource (lib "eagle-import") (part "HEADER-10P-SMD-2MM-MALE"))
    )
    (comp (ref "U1")
      (value "CC2591")
      (footprint "eagle-import:S-PVQFN-N16")
      (libsource (lib "eagle-import") (part "CC2591"))
    )
    (comp (ref "U2")
      (value "CC85XX")
      (footprint "eagle-import:S-PVQFN-N40")
      (libsource (lib "eagle-import") (part "CC85XX"))
    )
    (comp (ref "U3")
      (value "CS4270-TSSOP24")
      (footprint "eagle-import:TSSOP-24L")
      (libsource (lib "eagle-import") (part "CS4270-TSSOP24"))
    )
    (comp (ref "U4")
      (value "LM4881")
      (footprint "eagle-import:SO08")
      (libsource (lib "eagle-import") (part "LM4881"))
    )
    (comp (ref "U5")
      (value "MCP1826-SOT223")
      (footprint "eagle-import:SOT-223")
      (libsource (lib "eagle-import") (part "MCP1826-SOT223"))
    )
    (comp (ref "U6")
      (value "BQ2409XDGQ")
      (footprint "eagle-import:S-PDSO-G10")
      (libsource (lib "eagle-import") (part "BQ2409XDGQ"))
    )
    (comp (ref "U7")
      (value "TLV700DDC")
      (footprint "eagle-import:SOT-23-5")
      (libsource (lib "eagle-import") (part "TLV700DDC"))
    )
    (comp (ref "U8")
      (value "SN74LVC1G80DBV")
      (footprint "eagle-import:SOT-23-5")
      (libsource (lib "eagle-import") (part "SN74LVC1G80DBV"))
    )
    (comp (ref "U9")
      (value "CS2300-MSOP10L")
      (footprint "eagle-import:MSOP-10L")
      (libsource (lib "eagle-import") (part "CS2300-MSOP10L"))
    )
    (comp (ref "U10")
      (value "AT32UC3A3-LQFP-144")
      (footprint "eagle-import:LQFP-144")
      (libsource (lib "eagle-import") (part "AT32UC3A3-LQFP-144"))
    )
    (comp (ref "U11")
      (value "AT42QT1110-QFN-32")
      (footprint "eagle-import:QFN-32")
      (libsource (lib "eagle-import") (part "AT42QT1110-QFN-32"))
    )
    (comp (ref "USB")
      (value "USB_MICRO_AB")
      (footprint "eagle-import:USB_MICRO_AB")
      (libsource (lib "eagle-import") (part "USB_MICRO_AB"))
    )
    (comp (ref "VOL+")
      (value "TOUCH_PAD-CIRCLE-10MM")
      (footprint "eagle-import:TOUCH-CIRCLE-10MM")
      (libsource (lib "eagle-import") (part "TOUCH_PAD-CIRCLE-10MM"))
    )
    (comp (ref "VOL-")
      (value "TOUCH_PAD-CIRCLE-10MM")
      (footprint "eagle-import:TOUCH-CIRCLE-10MM")
      (libsource (lib "eagle-import") (part "TOUCH_PAD-CIRCLE-10MM"))
    )
    (comp (ref "WIRELESS")
      (value "TOUCH_PAD-CIRCLE-10MM")
      (footprint "eagle-import:TOUCH-CIRCLE-10MM")
      (libsource (lib "eagle-import") (part "TOUCH_PAD-CIRCLE-10MM"))
    )
    (comp (ref "X1")
      (value "48MHz")
      (footprint "eagle-import:ABM3C")
      (libsource (lib "eagle-import") (part "XTAL-ABRACONABM3C"))
    )
    (comp (ref "X2")
      (value "12MHz")
      (footprint "eagle-import:ABM8G")
      (libsource (lib "eagle-import") (part "XTAL-ABRACONABM8G"))
    )
  )
  (nets
    (net (code "1") (name "/ALL_GND") (class "Default")
      (node (ref "BATTERY") (pin "-") (pinfunction "N_-") (pintype "passive"))
      (node (ref "BATTERY") (pin "X1") (pinfunction "CASE_X1") (pintype "passive"))
      (node (ref "BATTERY") (pin "X2") (pinfunction "CASE_X2") (pintype "passive"))
      (node (ref "C59") (pin "2") (pinfunction "2_2") (pintype "passive"))
      (node (ref "C60") (pin "2") (pinfunction "2_2") (pintype "passive"))
      (node (ref "R24") (pin "1") (pinfunction "1_1") (pintype "passive"))
      (node (ref "R26") (pin "1") (pinfunction "1_1") (pintype "passive"))
      (node (ref "R37") (pin "1") (pinfunction "1_1") (pintype "passive"))
      (node (ref "R38") (pin "1") (pinfunction "1_1") (pintype "passive"))
      (node (ref "R39") (pin "1") (pinfunction "1_1") (pintype "passive"))
      (node (ref "U6") (pin "3") (pinfunction "VSS_3") (pintype "bidirectional"))
      (node (ref "U6") (pin "7") (pinfunction "ISET2_7") (pintype "bidirectional"))
      (node (ref "U6") (pin "GND") (pinfunction "VSS_GND") (pintype "bidirectional"))
      (node (ref "USB") (pin "5") (pinfunction "GND_5") (pintype "bidirectional"))
      (node (ref "USB") (pin "GND1") (pinfunction "GND_GND1") (pintype "bidirectional"))
      (node (ref "USB") (pin "GND2") (pinfunction "GND_GND2") (pintype "bidirectional"))
      (node (ref "USB") (pin "GND3") (pinfunction "GND_GND3") (pintype "bidirectional"))
      (node (ref "USB") (pin "GND4") (pinfunction "GND_GND4") (pintype "bidirectional"))
    )
    (net (code "2") (name "/AUX_VDD") (class "Default")
      (node (ref "C85") (pin "1") (pinfunction "1_1") (pintype "passive"))
      (node (ref "C86") (pin "1") (pinfunction "1_1") (pintype "passive"))
      (node (ref "R28") (pin "2") (pinfunction "2_2") (pintype "passive"))
      (node (ref "TO_MAIN1") (pin "1") (pinfunction "1_1") (pintype "bidirectional"))
      (node (ref "TO_MAIN1") (pin "3") (pinfunction "3_3") (pintype "bidirectional"))
      (node (ref "TO_MAIN1") (pin "5") (pinfunction "5_5") (pintype "bidirectional"))
      (node (ref "U11") (pin "18") (pinfunction "VDD_18") (pintype "bidirectional"))
      (node (ref "U11") (pin "4") (pinfunction "VDD_4") (pintype "bidirectional"))
    )
    (net (code "3") (name "/AUX_VDD2") (class "Default")
      (node (ref "LED_LL") (pin "2") (pinfunction "A_2") (pintype "passive"))
      (node (ref "LED_LL") (pin "2-2") (pinfunction "A_2-2") (pintype "passive"))
      (node (ref "LED_LR") (pin "2") (pinfunction "A_2") (pintype "passive"))
      (node (ref "LED_LR") (pin "2-2") (pinfunction "A_2-2") (pintype "passive"))
      (node (ref "LED_UL") (pin "2") (pinfunction "A_2") (pintype "passive"))
      (node (ref "LED_UL") (pin "2-2") (pinfunction "A_2-2") (pintype "passive"))
      (node (ref "LED_UR") (pin "2") (pinfunction "A_2") (pintype "passive"))
      (node (ref "LED_UR") (pin "2-2") (pinfunction "A_2-2") (pintype "passive"))
      (node (ref "TO_MAIN2") (pin "1") (pinfunction "1_1") (pintype "bidirectional"))
      (node (ref "TO_MAIN2") (pin "2") (pinfunction "2_2") (pintype "bidirectional"))
    )
    (net (code "4") (name "/AUX_VSS") (class "Default")
      (node (ref "C85") (pin "2") (pinfunction "2_2") (pintype "passive"))
      (node (ref "C86") (pin "2") (pinfunction "2_2") (pintype "passive"))
      (node (ref "TO_MAIN1") (pin "7") (pinfunction "7_7") (pintype "bidirectional"))
      (node (ref "TO_MAIN1") (pin "9") (pinfunction "9_9") (pintype "bidirectional"))
      (node (ref "U11") (pin "21") (pinfunction "VSS_21") (pintype "bidirectional"))
      (node (ref "U11") (pin "5") (pinfunction "VSS_5") (pintype "bidirectional"))
      (node (ref "U11") (pin "GND") (pinfunction "VSS_GND") (pintype "bidirectional"))
    )
    (net (code "5") (name "/AUX_VSS1") (class "Default")
      (node (ref "Q2") (pin "2") (pinfunction "S_2") (pintype "passive"))
      (node (ref "Q3") (pin "2") (pinfunction "S_2") (pintype "passive"))
      (node (ref "Q4") (pin "2") (pinfunction "S_2") (pintype "passive"))
      (node (ref "Q5") (pin "2") (pinfunction "S_2") (pintype "passive"))
      (node (ref "Q6") (pin "2") (pinfunction "S_2") (pintype "passive"))
      (node (ref "Q7") (pin "2") (pinfunction "S_2") (pintype "passive"))
      (node (ref "TO_MAIN2") (pin "10") (pinfunction "10_10") (pintype "bidirectional"))
      (node (ref "TO_MAIN2") (pin "9") (pinfunction "9_9") (pintype "bidirectional"))
    )
    (net (code "6") (name "/AUX_~{CHANGE}") (class "Default")
      (node (ref "TO_MAIN1") (pin "10") (pinfunction "10_10") (pintype "bidirectional"))
      (node (ref "U11") (pin "28") (pinfunction "~{CHANGE}_28") (pintype "bidirectional"))
    )
    (net (code "7") (name "/AVDD") (class "Default")
      (node (ref "C1") (pin "1") (pinfunction "1_1") (pintype "passive"))
      (node (ref "C10") (pin "1") (pinfunction "1_1") (pintype "passive"))
      (node (ref "C12") (pin "1") (pinfunction "1_1") (pintype "passive"))
      (node (ref "C13") (pin "1") (pinfunction "1_1") (pintype "passive"))
      (node (ref "C14") (pin "1") (pinfunction "1_1") (pintype "passive"))
      (node (ref "C15") (pin "1") (pinfunction "1_1") (pintype "passive"))
      (node (ref "C19") (pin "1") (pinfunction "1_1") (pintype "passive"))
      (node (ref "C20") (pin "1") (pinfunction "1_1") (pintype "passive"))
      (node (ref "C3") (pin "1") (pinfunction "1_1") (pintype "passive"))
      (node (ref "C4") (pin "1") (pinfunction "1_1") (pintype "passive"))
      (node (ref "C5") (pin "1") (pinfunction "1_1") (pintype "passive"))
      (node (ref "C7") (pin "1") (pinfunction "1_1") (pintype "passive"))
      (node (ref "C8") (pin "1") (pinfunction "1_1") (pintype "passive"))
      (node (ref "C9") (pin "1") (pinfunction "1_1") (pintype "passive"))
      (node (ref "L1") (pin "1") (pinfunction "1_1") (pintype "passive"))
      (node (ref "L2") (pin "1") (pinfunction "1_1") (pintype "passive"))
      (node (ref "R1") (pin "2") (pinfunction "2_2") (pintype "passive"))
      (node (ref "U1") (pin "1") (pinfunction "AVDD_PA1_1") (pintype "bidirectional"))
      (node (ref "U1") (pin "10") (pinfunction "AVDD_PA2_10") (pintype "bidirectional"))
      (node (ref "U1") (pin "13") (pinfunction "AVDD_LNA_13") (pintype "bidirectional"))
      (node (ref "U1") (pin "16") (pinfunction "AVDD_BIAS_16") (pintype "bidirectional"))
      (node (ref "U2") (pin "20") (pinfunction "AVDD1_20") (pintype "bidirectional"))
      (node (ref "U2") (pin "23") (pinfunction "AVDD2_23") (pintype "bidirectional"))
      (node (ref "U2") (pin "26") (pinfunction "AVDD3_26") (pintype "bidirectional"))
      (node (ref "U2") (pin "27") (pinfunction "AVDD4_27") (pintype "bidirectional"))
      (node (ref "U2") (pin "28") (pinfunction "AVDD5_28") (pintype "bidirectional"))
      (node (ref "U2") (pin "31") (pinfunction "AVDD6_31") (pintype "bidirectional"))
    )
    (net (code "8") (name "/AVDD_CODEC") (class "Default")
      (node (ref "C30") (pin "1") (pinfunction "1_1") (pintype "passive"))
      (node (ref "C31") (pin "1") (pinfunction "1_1") (pintype "passive"))
      (node (ref "C39") (pin "1") (pinfunction "1_1") (pintype "passive"))
      (node (ref "C64") (pin "1") (pinfunction "1_1") (pintype "passive"))
      (node (ref "C65") (pin "1") (pinfunction "1_1") (pintype "passive"))
      (node (ref "L15") (pin "1") (pinfunction "1_1") (pintype "passive"))
      (node (ref "L20") (pin "1") (pinfunction "1_1") (pintype "passive"))
      (node (ref "R10") (pin "2") (pinfunction "2_2") (pintype "passive"))
      (node (ref "R13") (pin "2") (pinfunction "2_2") (pintype "passive"))
      (node (ref "R16") (pin "2") (pinfunction "2_2") (pintype "passive"))
      (node (ref "U10") (pin "118") (pinfunction "VDDANA_118") (pintype "bidirectional"))
      (node (ref "U3") (pin "19") (pinfunction "VA_19") (pintype "bidirectional"))
      (node (ref "U4") (pin "6") (pinfunction "VDD_6") (pintype "bidirectional"))
    )
    (net (code "9") (name "/AVR_VDD") (class "Default")
      (node (ref "C32") (pin "1") (pinfunction "1_1") (pintype "passive"))
      (node (ref "C33") (pin "1") (pinfunction "1_1") (pintype "passive"))
      (node (ref "C34") (pin "1") (pinfunction "1_1") (pintype "passive"))
      (node (ref "C35") (pin "1") (pinfunction "1_1") (pintype "passive"))
      (node (ref "C37") (pin "1") (pinfunction "1_1") (pintype "passive"))
      (node (ref "C40") (pin "1") (pinfunction "1_1") (pintype "passive"))
      (node (ref "C41") (pin "1") (pinfunction "1_1") (pintype "passive"))
      (node (ref "C42") (pin "1") (pinfunction "1_1") (pintype "passive"))
      (node (ref "C43") (pin "1") (pinfunction "1_1") (pintype "passive"))
      (node (ref "C48") (pin "1") (pinfunction "1_1") (pintype "passive"))
      (node (ref "C49") (pin "1") (pinfunction "1_1") (pintype "passive"))
      (node (ref "C50") (pin "1") (pinfunction "1_1") (pintype "passive"))
      (node (ref "C51") (pin "1") (pinfunction "1_1") (pintype "passive"))
      (node (ref "C55") (pin "1") (pinfunction "1_1") (pintype "passive"))
      (node (ref "C56") (pin "1") (pinfunction "1_1") (pintype "passive"))
      (node (ref "C57") (pin "1") (pinfunction "1_1") (pintype "passive"))
      (node (ref "C58") (pin "1") (pinfunction "1_1") (pintype "passive"))
      (node (ref "C72") (pin "1") (pinfunction "1_1") (pintype "passive"))
      (node (ref "C74") (pin "1") (pinfunction "1_1") (pintype "passive"))
      (node (ref "C75") (pin "1") (pinfunction "1_1") (pintype "passive"))
      (node (ref "C77") (pin "1") (pinfunction "1_1") (pintype "passive"))
      (node (ref "C78") (pin "1") (pinfunction "1_1") (pintype "passive"))
      (node (ref "C95") (pin "1") (pinfunction "1_1") (pintype "passive"))
      (node (ref "JTAG") (pin "4") (pinfunction "4_4") (pintype "bidirectional"))
      (node (ref "L16") (pin "1") (pinfunction "1_1") (pintype "passive"))
      (node (ref "R18") (pin "2") (pinfunction "2_2") (pintype "passive"))
      (node (ref "R20") (pin "2") (pinfunction "2_2") (pintype "passive"))
      (node (ref "R22") (pin "2") (pinfunction "2_2") (pintype "passive"))
      (node (ref "R5") (pin "2") (pinfunction "2_2") (pintype "passive"))
      (node (ref "R8") (pin "2") (pinfunction "2_2") (pintype "passive"))
      (node (ref "SD1") (pin "VDD") (pinfunction "VDD_VDD") (pintype "bidirectional"))
      (node (ref "U10") (pin "10") (pinfunction "VDDIO_10") (pintype "bidirectional"))
      (node (ref "U10") (pin "103") (pinfunction "VDDIO_103") (pintype "bidirectional"))
      (node (ref "U10") (pin "130") (pinfunction "VDDIO_130") (pintype "bidirectional"))
      (node (ref "U10") (pin "142") (pinfunction "VDDIN_142") (pintype "bidirectional"))
      (node (ref "U10") (pin "143") (pinfunction "VDDIN_143") (pintype "bidirectional"))
      (node (ref "U10") (pin "2") (pinfunction "VDDIO_2") (pintype "bidirectional"))
      (node (ref "U10") (pin "21") (pinfunction "VDDIO_21") (pintype "bidirectional"))
      (node (ref "U10") (pin "48") (pinfunction "VDDIO_48") (pintype "bidirectional"))
      (node (ref "U10") (pin "64") (pinfunction "VDDIO_64") (pintype "bidirectional"))
      (node (ref "U10") (pin "81") (pinfunction "VDDIO_81") (pintype "bidirectional"))
    )
    (net (code "10") (name "/DVDD_CODEC") (class "Default")
      (node (ref "C28") (pin "1") (pinfunction "1_1") (pintype "passive"))
      (node (ref "C29") (pin "1") (pinfunction "1_1") (pintype "passive"))
      (node (ref "L14") (pin "1") (pinfunction "1_1") (pintype "passive"))
      (node (ref "U3") (pin "5") (pinfunction "VD_5") (pintype "bidirectional"))
      (node (ref "U3") (pin "8") (pinfunction "VLC_8") (pintype "bidirectional"))
    )
    (net (code "11") (name "/IOVDD") (class "Default")
      (node (ref "C11") (pin "1") (pinfunction "1_1") (pintype "passive"))
      (node (ref "C16") (pin "1") (pinfunction "1_1") (pintype "passive"))
      (node (ref "C17") (pin "1") (pinfunction "1_1") (pintype "passive"))
      (node (ref "C18") (pin "1") (pinfunction "1_1") (pintype "passive"))
      (node (ref "C2") (pin "1") (pinfunction "1_1") (pintype "passive"))
      (node (ref "C6") (pin "1") (pinfunction "1_1") (pintype "passive"))
      (node (ref "CC1") (pin "A") (pinfunction "A_A") (pintype "passive"))
      (node (ref "L3") (pin "1") (pinfunction "1_1") (pintype "passive"))
      (node (ref "U2") (pin "10") (pinfunction "IOVDD1_10") (pintype "bidirectional"))
      (node (ref "U2") (pin "12") (pinfunction "IOVDD2_12") (pintype "bidirectional"))
      (node (ref "U2") (pin "18") (pinfunction "IOVDD3_18") (pintype "bidirectional"))
      (node (ref "U2") (pin "37") (pinfunction "IOVDD4_37") (pintype "bidirectional"))
      (node (ref "U2") (pin "40") (pinfunction "DVDD_40") (pintype "bidirectional"))
    )
    (net (code "12") (name "/VBUS") (class "Default")
      (node (ref "C59") (pin "1") (pinfunction "1_1") (pintype "passive"))
      (node (ref "U10") (pin "1") (pinfunction "USB_VBUS_1") (pintype "bidirectional"))
      (node (ref "U6") (pin "1") (pinfunction "IN_1") (pintype "bidirectional"))
      (node (ref "USB") (pin "1") (pinfunction "VBUS_1") (pintype "bidirectional"))
    )
    (net (code "13") (name "/~{AVR_LED0}") (class "Default")
      (node (ref "AVR") (pin "C") (pinfunction "C_C") (pintype "passive"))
      (node (ref "U10") (pin "50") (pinfunction "PX08_50") (pintype "bidirectional"))
    )
    (net (code "14") (name "/~{AVR_LED1}") (class "Default")
      (node (ref "AVR1") (pin "C") (pinfunction "C_C") (pintype "passive"))
      (node (ref "U10") (pin "40") (pinfunction "PX15_40") (pintype "bidirectional"))
    )
    (net (code "15") (name "/~{CHANGE}") (class "Default")
      (node (ref "TO_AUX2") (pin "9") (pinfunction "9_9") (pintype "bidirectional"))
      (node (ref "U10") (pin "34") (pinfunction "PX12_34") (pintype "bidirectional"))
    )
    (net (code "16") (name "/~{CS_CC8531}") (class "Default")
      (node (ref "CC_DEBUG") (pin "5") (pinfunction "5_5") (pintype "bidirectional"))
      (node (ref "U10") (pin "133") (pinfunction "PA07_133") (pintype "bidirectional"))
      (node (ref "U2") (pin "3") (pinfunction "~{CS}_3") (pintype "bidirectional"))
    )
    (net (code "17") (name "/~{CS_CLOCK}") (class "Default")
      (node (ref "U10") (pin "100") (pinfunction "PA14_100") (pintype "bidirectional"))
      (node (ref "U9") (pin "8") (pinfunction "AD0/~{CS}_8") (pintype "bidirectional"))
    )
    (net (code "18") (name "/~{CS_CODEC}") (class "Default")
      (node (ref "U10") (pin "93") (pinfunction "PX32_93") (pintype "bidirectional"))
      (node (ref "U3") (pin "11") (pinfunction "AD0/~{CS}_11") (pintype "bidirectional"))
    )
    (net (code "19") (name "/~{CS_TOUCH}") (class "Default")
      (node (ref "TO_AUX2") (pin "7") (pinfunction "7_7") (pintype "bidirectional"))
      (node (ref "U10") (pin "51") (pinfunction "PX38_51") (pintype "bidirectional"))
    )
    (net (code "20") (name "/~{GPIO}") (class "Default")
      (node (ref "GPIO") (pin "2") (pinfunction "2_2") (pintype "bidirectional"))
      (node (ref "U10") (pin "74") (pinfunction "PX46_74") (pintype "bidirectional"))
    )
    (net (code "21") (name "/~{MUTE_L}") (class "Default")
      (node (ref "U10") (pin "96") (pinfunction "PX30_96") (pintype "bidirectional"))
      (node (ref "U3") (pin "21") (pinfunction "~{MUTEA}_21") (pintype "bidirectional"))
    )
    (net (code "22") (name "/~{MUTE_R}") (class "Default")
      (node (ref "U10") (pin "95") (pinfunction "PX33_95") (pintype "bidirectional"))
      (node (ref "U3") (pin "24") (pinfunction "~{MUTEB}_24") (pintype "bidirectional"))
    )
    (net (code "23") (name "/~{PAIR}") (class "Default")
      (node (ref "U10") (pin "129") (pinfunction "PA13_129") (pintype "bidirectional"))
      (node (ref "U2") (pin "7") (pinfunction "GIO1_7") (pintype "bidirectional"))
    )
    (net (code "24") (name "/~{RESET_CC8531}") (class "Default")
      (node (ref "CC_DEBUG") (pin "7") (pinfunction "7_7") (pintype "bidirectional"))
      (node (ref "L7") (pin "2") (pinfunction "2_2") (pintype "passive"))
      (node (ref "U10") (pin "127") (pinfunction "PA06_127") (pintype "bidirectional"))
    )
    (net (code "25") (name "/~{RESET_CODEC}") (class "Default")
      (node (ref "U10") (pin "97") (pinfunction "PX31_97") (pintype "bidirectional"))
      (node (ref "U3") (pin "14") (pinfunction "~{RESET}_14") (pintype "bidirectional"))
    )
    (net (code "26") (name "/~{RESET}") (class "Default")
      (node (ref "C73") (pin "1") (pinfunction "1_1") (pintype "passive"))
      (node (ref "JTAG") (pin "6") (pinfunction "6_6") (pintype "bidirectional"))
      (node (ref "R18") (pin "1") (pinfunction "1_1") (pintype "passive"))
      (node (ref "RESET") (pin "1") (pinfunction "1_1") (pintype "bidirectional"))
      (node (ref "U10") (pin "106") (pinfunction "~{RESET}_106") (pintype "bidirectional"))
    )
    (net (code "27") (name "/~{SD_CARD}") (class "Default")
      (node (ref "SD1") (pin "SWB") (pinfunction "SWB_SWB") (pintype "bidirectional"))
      (node (ref "U10") (pin "27") (pinfunction "PB01_27") (pintype "bidirectional"))
    )
    (net (code "28") (name "A3.3V") (class "Default")
      (node (ref "C70") (pin "1") (pinfunction "1_1") (pintype "passive"))
      (node (ref "L15") (pin "2") (pinfunction "2_2") (pintype "passive"))
      (node (ref "L20") (pin "2") (pinfunction "2_2") (pintype "passive"))
      (node (ref "U7") (pin "5") (pinfunction "VOUT_5") (pintype "bidirectional"))
    )
    (net (code "29") (name "AGND") (class "Default")
      (node (ref "C30") (pin "2") (pinfunction "2_2") (pintype "passive"))
      (node (ref "C31") (pin "2") (pinfunction "2_2") (pintype "passive"))
      (node (ref "C39") (pin "2") (pinfunction "2_2") (pintype "passive"))
      (node (ref "C44") (pin "2") (pinfunction "2_2") (pintype "passive"))
      (node (ref "C45") (pin "2") (pinfunction "2_2") (pintype "passive"))
      (node (ref "C46") (pin "2") (pinfunction "2_2") (pintype "passive"))
      (node (ref "C47") (pin "2") (pinfunction "2_2") (pintype "passive"))
      (node (ref "C63") (pin "2") (pinfunction "2_2") (pintype "passive"))
      (node (ref "C64") (pin "2") (pinfunction "2_2") (pintype "passive"))
      (node (ref "C65") (pin "2") (pinfunction "2_2") (pintype "passive"))
      (node (ref "C70") (pin "2") (pinfunction "2_2") (pintype "passive"))
      (node (ref "C71") (pin "2") (pinfunction "2_2") (pintype "passive"))
      (node (ref "C98") (pin "2") (pinfunction "2_2") (pintype "passive"))
      (node (ref "C99") (pin "2") (pinfunction "2_2") (pintype "passive"))
      (node (ref "LINE_IN") (pin "5") (pinfunction "GND_5") (pintype "bidirectional"))
      (node (ref "PHONE_OUT") (pin "5") (pinfunction "GND_5") (pintype "bidirectional"))
      (node (ref "R19") (pin "1") (pinfunction "1_1") (pintype "passive"))
      (node (ref "R24") (pin "2") (pinfunction "2_2") (pintype "passive"))
      (node (ref "R25") (pin "1") (pinfunction "1_1") (pintype "passive"))
      (node (ref "U10") (pin "117") (pinfunction "GNDANA_117") (pintype "bidirectional"))
      (node (ref "U3") (pin "20") (pinfunction "AGND_20") (pintype "bidirectional"))
      (node (ref "U4") (pin "2") (pinfunction "VSS_2") (pintype "bidirectional"))
      (node (ref "U7") (pin "2") (pinfunction "GND_2") (pintype "bidirectional"))
    )
    (net (code "30") (name "AUDIO") (class "Default")
      (node (ref "C53") (pin "1") (pinfunction "1_1") (pintype "passive"))
      (node (ref "R7") (pin "1") (pinfunction "1_1") (pintype "passive"))
      (node (ref "U10") (pin "116") (pinfunction "PA17_116") (pintype "bidirectional"))
      (node (ref "U4") (pin "7") (pinfunction "OUTA_7") (pintype "bidirectional"))
    )
    (net (code "31") (name "AUX_BLUE_BOT") (class "Default")
      (node (ref "Q7") (pin "1") (pinfunction "G_1") (pintype "passive"))
      (node (ref "TO_MAIN2") (pin "7") (pinfunction "7_7") (pintype "bidirectional"))
    )
    (net (code "32") (name "AUX_BLUE_TOP") (class "Default")
      (node (ref "Q6") (pin "1") (pinfunction "G_1") (pintype "passive"))
      (node (ref "TO_MAIN2") (pin "4") (pinfunction "4_4") (pintype "bidirectional"))
    )
    (net (code "33") (name "AUX_CS") (class "Default")
      (node (ref "TO_MAIN1") (pin "8") (pinfunction "8_8") (pintype "bidirectional"))
      (node (ref "U11") (pin "14") (pinfunction "~{SS}_14") (pintype "bidirectional"))
    )
    (net (code "34") (name "AUX_GREEN_BOT") (class "Default")
      (node (ref "Q5") (pin "1") (pinfunction "G_1") (pintype "passive"))
      (node (ref "TO_MAIN2") (pin "5") (pinfunction "5_5") (pintype "bidirectional"))
    )
    (net (code "35") (name "AUX_GREEN_TOP") (class "Default")
      (node (ref "Q4") (pin "1") (pinfunction "G_1") (pintype "passive"))
      (node (ref "TO_MAIN2") (pin "6") (pinfunction "6_6") (pintype "bidirectional"))
    )
    (net (code "36") (name "AUX_MISO") (class "Default")
      (node (ref "TO_MAIN1") (pin "4") (pinfunction "4_4") (pintype "bidirectional"))
      (node (ref "U11") (pin "16") (pinfunction "MISO_16") (pintype "bidirectional"))
    )
    (net (code "37") (name "AUX_MOSI") (class "Default")
      (node (ref "TO_MAIN1") (pin "6") (pinfunction "6_6") (pintype "bidirectional"))
      (node (ref "U11") (pin "15") (pinfunction "MOSI_15") (pintype "bidirectional"))
    )
    (net (code "38") (name "AUX_RED_BOT") (class "Default")
      (node (ref "Q3") (pin "1") (pinfunction "G_1") (pintype "passive"))
      (node (ref "TO_MAIN2") (pin "3") (pinfunction "3_3") (pintype "bidirectional"))
    )
    (net (code "39") (name "AUX_RED_TOP") (class "Default")
      (node (ref "Q2") (pin "1") (pinfunction "G_1") (pintype "passive"))
      (node (ref "TO_MAIN2") (pin "8") (pinfunction "8_8") (pintype "bidirectional"))
    )
    (net (code "40") (name "AUX_SCLK") (class "Default")
      (node (ref "TO_MAIN1") (pin "2") (pinfunction "2_2") (pintype "bidirectional"))
      (node (ref "U11") (pin "17") (pinfunction "SCK_17") (pintype "bidirectional"))
    )
    (net (code "41") (name "BAT") (class "Default")
      (node (ref "BATTERY") (pin "+") (pinfunction "P_+") (pintype "passive"))
      (node (ref "C60") (pin "1") (pinfunction "1_1") (pintype "passive"))
      (node (ref "F1") (pin "1") (pinfunction "1_1") (pintype "passive"))
      (node (ref "R11") (pin "2") (pinfunction "2_2") (pintype "passive"))
      (node (ref "U2") (pin "29") (pinfunction "VBAT_29") (pintype "bidirectional"))
      (node (ref "U6") (pin "10") (pinfunction "OUT_10") (pintype "bidirectional"))
    )
    (net (code "42") (name "BCLK") (class "Default")
      (node (ref "L9") (pin "1") (pinfunction "1_1") (pintype "passive"))
      (node (ref "U10") (pin "61") (pinfunction "PX34_61") (pintype "bidirectional"))
      (node (ref "U10") (pin "85") (pinfunction "PX23_85") (pintype "bidirectional"))
      (node (ref "U10") (pin "91") (pinfunction "PX28_91") (pintype "bidirectional"))
      (node (ref "U3") (pin "4") (pinfunction "BCLK_4") (pintype "bidirectional"))
    )
    (net (code "43") (name "BLUE_BOT") (class "Default")
      (node (ref "TO_AUX1") (pin "8") (pinfunction "8_8") (pintype "bidirectional"))
      (node (ref "U10") (pin "84") (pinfunction "PX18_84") (pintype "bidirectional"))
    )
    (net (code "44") (name "BLUE_TOP") (class "Default")
      (node (ref "TO_AUX1") (pin "3") (pinfunction "3_3") (pintype "bidirectional"))
      (node (ref "U10") (pin "68") (pinfunction "PX14_68") (pintype "bidirectional"))
    )
    (net (code "45") (name "CTS") (class "Default")
      (node (ref "SERIAL") (pin "5") (pinfunction "5_5") (pintype "bidirectional"))
      (node (ref "U10") (pin "62") (pinfunction "PX02_62") (pintype "bidirectional"))
    )
    (net (code "46") (name "D+_UC") (class "Default")
      (node (ref "R15") (pin "2") (pinfunction "2_2") (pintype "passive"))
      (node (ref "U10") (pin "6") (pinfunction "D+_HS_6") (pintype "bidirectional"))
      (node (ref "USB") (pin "3") (pinfunction "D+_3") (pintype "bidirectional"))
    )
    (net (code "47") (name "D-_UC") (class "Default")
      (node (ref "R17") (pin "2") (pinfunction "2_2") (pintype "passive"))
      (node (ref "U10") (pin "5") (pinfunction "D-_HS_5") (pintype "bidirectional"))
      (node (ref "USB") (pin "2") (pinfunction "D-_2") (pintype "bidirectional"))
    )
    (net (code "48") (name "D3.3V") (class "Default")
      (node (ref "C61") (pin "1") (pinfunction "1_1") (pintype "passive"))
      (node (ref "C79") (pin "1") (pinfunction "1_1") (pintype "passive"))
      (node (ref "C80") (pin "1") (pinfunction "1_1") (pintype "passive"))
      (node (ref "C81") (pin "1") (pinfunction "1_1") (pintype "passive"))
      (node (ref "CC_DEBUG") (pin "2") (pinfunction "2_2") (pintype "bidirectional"))
      (node (ref "L1") (pin "2") (pinfunction "2_2") (pintype "passive"))
      (node (ref "L14") (pin "2") (pinfunction "2_2") (pintype "passive"))
      (node (ref "L16") (pin "2") (pinfunction "2_2") (pintype "passive"))
      (node (ref "L17") (pin "2") (pinfunction "2_2") (pintype "passive"))
      (node (ref "L19") (pin "2") (pinfunction "2_2") (pintype "passive"))
      (node (ref "L2") (pin "2") (pinfunction "2_2") (pintype "passive"))
      (node (ref "L3") (pin "2") (pinfunction "2_2") (pintype "passive"))
      (node (ref "R12") (pin "2") (pinfunction "2_2") (pintype "passive"))
      (node (ref "U5") (pin "3") (pinfunction "VOUT_3") (pintype "bidirectional"))
      (node (ref "U8") (pin "5") (pinfunction "VCC_5") (pintype "bidirectional"))
      (node (ref "U9") (pin "1") (pinfunction "VD_1") (pintype "bidirectional"))
    )
    (net (code "49") (name "DAC0_N") (class "Default")
      (node (ref "U10") (pin "126") (pinfunction "PA04_126") (pintype "bidirectional"))
    )
    (net (code "50") (name "DAC0_P") (class "Default")
      (node (ref "U10") (pin "125") (pinfunction "PA03_125") (pintype "bidirectional"))
    )
    (net (code "51") (name "DAC1_N") (class "Default")
      (node (ref "U10") (pin "112") (pinfunction "PA24_112") (pintype "bidirectional"))
    )
    (net (code "52") (name "DAC1_P") (class "Default")
      (node (ref "U10") (pin "111") (pinfunction "PA23_111") (pintype "bidirectional"))
    )
    (net (code "53") (name "DGND") (class "Default")
      (node (ref "C1") (pin "2") (pinfunction "2_2") (pintype "passive"))
      (node (ref "C10") (pin "2") (pinfunction "2_2") (pintype "passive"))
      (node (ref "C11") (pin "2") (pinfunction "2_2") (pintype "passive"))
      (node (ref "C12") (pin "2") (pinfunction "2_2") (pintype "passive"))
      (node (ref "C13") (pin "2") (pinfunction "2_2") (pintype "passive"))
      (node (ref "C14") (pin "2") (pinfunction "2_2") (pintype "passive"))
      (node (ref "C15") (pin "2") (pinfunction "2_2") (pintype "passive"))
      (node (ref "C16") (pin "2") (pinfunction "2_2") (pintype "passive"))
      (node (ref "C17") (pin "2") (pinfunction "2_2") (pintype "passive"))
      (node (ref "C18") (pin "2") (pinfunction "2_2") (pintype "passive"))
      (node (ref "C19") (pin "2") (pinfunction "2_2") (pintype "passive"))
      (node (ref "C2") (pin "2") (pinfunction "2_2") (pintype "passive"))
      (node (ref "C20") (pin "2") (pinfunction "2_2") (pintype "passive"))
      (node (ref "C23") (pin "2") (pinfunction "2_2") (pintype "passive"))
      (node (ref "C24") (pin "2") (pinfunction "2_2") (pintype "passive"))
      (node (ref "C25") (pin "2") (pinfunction "2_2") (pintype "passive"))
      (node (ref "C26") (pin "2") (pinfunction "2_2") (pintype "passive"))
      (node (ref "C27") (pin "2") (pinfunction "2_2") (pintype "passive"))
      (node (ref "C28") (pin "2") (pinfunction "2_2") (pintype "passive"))
      (node (ref "C29") (pin "2") (pinfunction "2_2") (pintype "passive"))
      (node (ref "C3") (pin "2") (pinfunction "2_2") (pintype "passive"))
      (node (ref "C32") (pin "2") (pinfunction "2_2") (pintype "passive"))
      (node (ref "C33") (pin "2") (pinfunction "2_2") (pintype "passive"))
      (node (ref "C34") (pin "2") (pinfunction "2_2") (pintype "passive"))
      (node (ref "C35") (pin "2") (pinfunction "2_2") (pintype "passive"))
      (node (ref "C37") (pin "2") (pinfunction "2_2") (pintype "passive"))
      (node (ref "C4") (pin "2") (pinfunction "2_2") (pintype "passive"))
      (node (ref "C40") (pin "2") (pinfunction "2_2") (pintype "passive"))
      (node (ref "C41") (pin "2") (pinfunction "2_2") (pintype "passive"))
      (node (ref "C42") (pin "2") (pinfunction "2_2") (pintype "passive"))
      (node (ref "C43") (pin "2") (pinfunction "2_2") (pintype "passive"))
      (node (ref "C48") (pin "2") (pinfunction "2_2") (pintype "passive"))
      (node (ref "C49") (pin "2") (pinfunction "2_2") (pintype "passive"))
      (node (ref "C5") (pin "2") (pinfunction "2_2") (pintype "passive"))
      (node (ref "C50") (pin "2") (pinfunction "2_2") (pintype "passive"))
      (node (ref "C51") (pin "2") (pinfunction "2_2") (pintype "passive"))
      (node (ref "C54") (pin "2") (pinfunction "2_2") (pintype "passive"))
      (node (ref "C55") (pin "2") (pinfunction "2_2") (pintype "passive"))
      (node (ref "C56") (pin "2") (pinfunction "2_2") (pintype "passive"))
      (node (ref "C57") (pin "2") (pinfunction "2_2") (pintype "passive"))
      (node (ref "C58") (pin "2") (pinfunction "2_2") (pintype "passive"))
      (node (ref "C6") (pin "2") (pinfunction "2_2") (pintype "passive"))
      (node (ref "C61") (pin "2") (pinfunction "2_2") (pintype "passive"))
      (node (ref "C62") (pin "2") (pinfunction "2_2") (pintype "passive"))
      (node (ref "C68") (pin "2") (pinfunction "2_2") (pintype "passive"))
      (node (ref "C69") (pin "2") (pinfunction "2_2") (pintype "passive"))
      (node (ref "C7") (pin "2") (pinfunction "2_2") (pintype "passive"))
      (node (ref "C72") (pin "2") (pinfunction "2_2") (pintype "passive"))
      (node (ref "C73") (pin "2") (pinfunction "2_2") (pintype "passive"))
      (node (ref "C74") (pin "2") (pinfunction "2_2") (pintype "passive"))
      (node (ref "C75") (pin "2") (pinfunction "2_2") (pintype "passive"))
      (node (ref "C76") (pin "2") (pinfunction "2_2") (pintype "passive"))
      (node (ref "C77") (pin "2") (pinfunction "2_2") (pintype "passive"))
      (node (ref "C78") (pin "2") (pinfunction "2_2") (pintype "passive"))
      (node (ref "C79") (pin "2") (pinfunction "2_2") (pintype "passive"))
      (node (ref "C8") (pin "2") (pinfunction "2_2") (pintype "passive"))
      (node (ref "C80") (pin "2") (pinfunction "2_2") (pintype "passive"))
      (node (ref "C81") (pin "2") (pinfunction "2_2") (pintype "passive"))
      (node (ref "C82") (pin "2") (pinfunction "2_2") (pintype "passive"))
      (node (ref "C83") (pin "2") (pinfunction "2_2") (pintype "passive"))
      (node (ref "C84") (pin "2") (pinfunction "2_2") (pintype "passive"))
      (node (ref "C9") (pin "2") (pinfunction "2_2") (pintype "passive"))
      (node (ref "C95") (pin "2") (pinfunction "2_2") (pintype "passive"))
      (node (ref "CC_DEBUG") (pin "1") (pinfunction "1_1") (pintype "bidirectional"))
      (node (ref "GPIO") (pin "4") (pinfunction "4_4") (pintype "bidirectional"))
      (node (ref "JTAG") (pin "10") (pinfunction "10_10") (pintype "bidirectional"))
      (node (ref "JTAG") (pin "2") (pinfunction "2_2") (pintype "bidirectional"))
      (node (ref "L6") (pin "1") (pinfunction "1_1") (pintype "passive"))
      (node (ref "POWER") (pin "C") (pinfunction "C_C") (pintype "passive"))
      (node (ref "R2") (pin "1") (pinfunction "1_1") (pintype "passive"))
      (node (ref "R26") (pin "2") (pinfunction "2_2") (pintype "passive"))
      (node (ref "R27") (pin "1") (pinfunction "1_1") (pintype "passive"))
      (node (ref "R3") (pin "1") (pinfunction "1_1") (pintype "passive"))
      (node (ref "R6") (pin "1") (pinfunction "1_1") (pintype "passive"))
      (node (ref "RESET") (pin "3") (pinfunction "3_3") (pintype "bidirectional"))
      (node (ref "SD1") (pin "GND1") (pinfunction "GND_GND1") (pintype "bidirectional"))
      (node (ref "SD1") (pin "GND2") (pinfunction "GND_GND2") (pintype "bidirectional"))
      (node (ref "SD1") (pin "GND3") (pinfunction "GND_GND3") (pintype "bidirectional"))
      (node (ref "SD1") (pin "GND4") (pinfunction "GND_GND4") (pintype "bidirectional"))
      (node (ref "SD1") (pin "SWA") (pinfunction "SWA_SWA") (pintype "bidirectional"))
      (node (ref "SD1") (pin "VSS") (pinfunction "GND_VSS") (pintype "bidirectional"))
      (node (ref "SERIAL") (pin "6") (pinfunction "6_6") (pintype "bidirectional"))
      (node (ref "SMA") (pin "GND1") (pinfunction "GND_GND1") (pintype "bidirectional"))
      (node (ref "SMA") (pin "GND2") (pinfunction "GND_GND2") (pintype "bidirectional"))
      (node (ref "SMA") (pin "GND3") (pinfunction "GND_GND3") (pintype "bidirectional"))
      (node (ref "SMA") (pin "GND4") (pinfunction "GND_GND4") (pintype "bidirectional"))
      (node (ref "TO_AUX1") (pin "10") (pinfunction "10_10") (pintype "bidirectional"))
      (node (ref "TO_AUX1") (pin "9") (pinfunction "9_9") (pintype "bidirectional"))
      (node (ref "TO_AUX2") (pin "10") (pinfunction "10_10") (pintype "bidirectional"))
      (node (ref "TO_AUX2") (pin "6") (pinfunction "6_6") (pintype "bidirectional"))
      (node (ref "TO_AUX2") (pin "8") (pinfunction "8_8") (pintype "bidirectional"))
      (node (ref "U1") (pin "12") (pinfunction "GND_12") (pintype "bidirectional"))
      (node (ref "U1") (pin "14") (pinfunction "GND_14") (pintype "bidirectional"))
      (node (ref "U1") (pin "8") (pinfunction "GND_8") (pintype "bidirectional"))
      (node (ref "U1") (pin "9") (pinfunction "GND_9") (pintype "bidirectional"))
      (node (ref "U1") (pin "GND") (pinfunction "GND_GND") (pintype "bidirectional"))
      (node (ref "U10") (pin "102") (pinfunction "GNDIO_102") (pintype "bidirectional"))
      (node (ref "U10") (pin "131") (pinfunction "GNDIO_131") (pintype "bidirectional"))
      (node (ref "U10") (pin "140") (pinfunction "GNDCORE_140") (pintype "bidirectional"))
      (node (ref "U10") (pin "144") (pinfunction "GNDPLL_144") (pintype "bidirectional"))
      (node (ref "U10") (pin "20") (pinfunction "GNDIO_20") (pintype "bidirectional"))
      (node (ref "U10") (pin "4") (pinfunction "GNDIO_4") (pintype "bidirectional"))
      (node (ref "U10") (pin "47") (pinfunction "GNDIO_47") (pintype "bidirectional"))
      (node (ref "U10") (pin "65") (pinfunction "GNDIO_65") (pintype "bidirectional"))
      (node (ref "U10") (pin "7") (pinfunction "GNDIO_7") (pintype "bidirectional"))
      (node (ref "U10") (pin "82") (pinfunction "GNDIO_82") (pintype "bidirectional"))
      (node (ref "U2") (pin "19") (pinfunction "AD2/GIO9_19") (pintype "bidirectional"))
      (node (ref "U2") (pin "32") (pinfunction "SCL/GIO10_32") (pintype "bidirectional"))
      (node (ref "U2") (pin "33") (pinfunction "SDA/GIO11_33") (pintype "bidirectional"))
      (node (ref "U2") (pin "34") (pinfunction "GIO12_34") (pintype "bidirectional"))
      (node (ref "U2") (pin "35") (pinfunction "GIO13_35") (pintype "bidirectional"))
      (node (ref "U2") (pin "GND") (pinfunction "GND_GND") (pintype "bidirectional"))
      (node (ref "U3") (pin "6") (pinfunction "DGND_6") (pintype "bidirectional"))
      (node (ref "U5") (pin "2") (pinfunction "GND_2") (pintype "bidirectional"))
      (node (ref "U5") (pin "4") (pinfunction "GND_4") (pintype "bidirectional"))
      (node (ref "U8") (pin "3") (pinfunction "GND_3") (pintype "bidirectional"))
      (node (ref "U9") (pin "2") (pinfunction "GND_2") (pintype "bidirectional"))
      (node (ref "U9") (pin "7") (pinfunction "FILTN_7") (pintype "bidirectional"))
      (node (ref "X1") (pin "2") (pinfunction "CASE_2") (pintype "passive"))
      (node (ref "X1") (pin "4") (pinfunction "CASE_4") (pintype "passive"))
      (node (ref "X2") (pin "GND-1") (pinfunction "CASE_GND-1") (pintype "passive"))
      (node (ref "X2") (pin "GND-2") (pinfunction "CASE_GND-2") (pintype "passive"))
    )
    (net (code "54") (name "DIN") (class "Default")
      (node (ref "L13") (pin "1") (pinfunction "1_1") (pintype "passive"))
      (node (ref "U10") (pin "86") (pinfunction "PX24_86") (pintype "bidirectional"))
      (node (ref "U3") (pin "1") (pinfunction "DIN_1") (pintype "bidirectional"))
    )
    (net (code "55") (name "DOUT") (class "Default")
      (node (ref "L11") (pin "1") (pinfunction "1_1") (pintype "passive"))
      (node (ref "U10") (pin "92") (pinfunction "PX25_92") (pintype "bidirectional"))
      (node (ref "U3") (pin "7") (pinfunction "DOUT_7") (pintype "bidirectional"))
    )
    (net (code "56") (name "GREEN_BOT") (class "Default")
      (node (ref "TO_AUX1") (pin "6") (pinfunction "6_6") (pintype "bidirectional"))
      (node (ref "U10") (pin "139") (pinfunction "PA09_139") (pintype "bidirectional"))
    )
    (net (code "57") (name "GREEN_TOP") (class "Default")
      (node (ref "TO_AUX1") (pin "5") (pinfunction "5_5") (pintype "bidirectional"))
      (node (ref "U10") (pin "75") (pinfunction "PX50_75") (pintype "bidirectional"))
    )
    (net (code "58") (name "IN_L") (class "Default")
      (node (ref "C38") (pin "1") (pinfunction "1_1") (pintype "passive"))
      (node (ref "LINE_IN") (pin "4") (pinfunction "L_4") (pintype "bidirectional"))
      (node (ref "R19") (pin "2") (pinfunction "2_2") (pintype "passive"))
    )
    (net (code "59") (name "IN_R") (class "Default")
      (node (ref "C36") (pin "1") (pinfunction "1_1") (pintype "passive"))
      (node (ref "LINE_IN") (pin "1") (pinfunction "R_1") (pintype "bidirectional"))
    )
    (net (code "60") (name "LINEIN_SENSE") (class "Default")
      (node (ref "LINE_IN") (pin "3") (pinfunction "L_SW_3") (pintype "bidirectional"))
      (node (ref "R13") (pin "1") (pinfunction "1_1") (pintype "passive"))
      (node (ref "U10") (pin "114") (pinfunction "PA19_114") (pintype "bidirectional"))
    )
    (net (code "61") (name "LNA_EN") (class "Default")
      (node (ref "U1") (pin "6") (pinfunction "EN_6") (pintype "bidirectional"))
      (node (ref "U2") (pin "38") (pinfunction "XLNAEN_38") (pintype "bidirectional"))
    )
    (net (code "62") (name "MCI-CLK") (class "Default")
      (node (ref "SD1") (pin "CLK") (pinfunction "CLK/SCLK_CLK") (pintype "bidirectional"))
      (node (ref "U10") (pin "26") (pinfunction "PA27_26") (pintype "bidirectional"))
    )
    (net (code "63") (name "MCI-CMD") (class "Default")
      (node (ref "R22") (pin "1") (pinfunction "1_1") (pintype "passive"))
      (node (ref "SD1") (pin "CMD") (pinfunction "CMD/MOSI_CMD") (pintype "bidirectional"))
      (node (ref "U10") (pin "28") (pinfunction "PA28_28") (pintype "bidirectional"))
    )
    (net (code "64") (name "MCI-DATA0") (class "Default")
      (node (ref "R20") (pin "1") (pinfunction "1_1") (pintype "passive"))
      (node (ref "SD1") (pin "DAT0") (pinfunction "DAT0/MISO_DAT0") (pintype "bidirectional"))
      (node (ref "U10") (pin "23") (pinfunction "PA29_23") (pintype "bidirectional"))
    )
    (net (code "65") (name "MCI-DATA1") (class "Default")
      (node (ref "SD1") (pin "DAT1") (pinfunction "DAT1/NC_DAT1") (pintype "bidirectional"))
      (node (ref "U10") (pin "14") (pinfunction "PA30_14") (pintype "bidirectional"))
    )
    (net (code "66") (name "MCI-DATA2") (class "Default")
      (node (ref "SD1") (pin "DAT2") (pinfunction "DAT2/NC_DAT2") (pintype "bidirectional"))
      (node (ref "U10") (pin "29") (pinfunction "PA31_29") (pintype "bidirectional"))
    )
    (net (code "67") (name "MCI-DATA3") (class "Default")
      (node (ref "SD1") (pin "CD/DAT3") (pinfunction "CD/DAT3/~{CS}_CD/DAT3") (pintype "bidirectional"))
      (node (ref "U10") (pin "30") (pinfunction "PB00_30") (pintype "bidirectional"))
    )
    (net (code "68") (name "MCLK") (class "Default")
      (node (ref "L8") (pin "1") (pinfunction "1_1") (pintype "passive"))
      (node (ref "U3") (pin "3") (pinfunction "MCLK_3") (pintype "bidirectional"))
      (node (ref "U8") (pin "2") (pinfunction "CLK_2") (pintype "bidirectional"))
      (node (ref "U9") (pin "3") (pinfunction "CLK_OUT_3") (pintype "bidirectional"))
    )
    (net (code "69") (name "MISO0") (class "Default")
      (node (ref "CC_DEBUG") (pin "10") (pinfunction "10_10") (pintype "bidirectional"))
      (node (ref "U10") (pin "136") (pinfunction "PA11_136") (pintype "bidirectional"))
      (node (ref "U2") (pin "6") (pinfunction "MISO_6") (pintype "bidirectional"))
      (node (ref "U3") (pin "9") (pinfunction "SDA/MISO_9") (pintype "bidirectional"))
    )
    (net (code "70") (name "MISO1") (class "Default")
      (node (ref "TO_AUX2") (pin "3") (pinfunction "3_3") (pintype "bidirectional"))
      (node (ref "U10") (pin "11") (pinfunction "PB08_11") (pintype "bidirectional"))
    )
    (net (code "71") (name "MOSI0") (class "Default")
      (node (ref "CC_DEBUG") (pin "8") (pinfunction "8_8") (pintype "bidirectional"))
      (node (ref "U10") (pin "138") (pinfunction "PA10_138") (pintype "bidirectional"))
      (node (ref "U2") (pin "5") (pinfunction "MOSI_5") (pintype "bidirectional"))
      (node (ref "U3") (pin "12") (pinfunction "AD1/MOSI_12") (pintype "bidirectional"))
      (node (ref "U9") (pin "10") (pinfunction "SDA/MOSI_10") (pintype "bidirectional"))
    )
    (net (code "72") (name "MOSI1") (class "Default")
      (node (ref "TO_AUX2") (pin "5") (pinfunction "5_5") (pintype "bidirectional"))
      (node (ref "U10") (pin "16") (pinfunction "PB10_16") (pintype "bidirectional"))
    )
    (net (code "73") (name "Net-(AVR-PadA)") (class "Default")
      (node (ref "AVR") (pin "A") (pinfunction "A_A") (pintype "passive"))
      (node (ref "R8") (pin "1") (pinfunction "1_1") (pintype "passive"))
    )
    (net (code "74") (name "Net-(AVR1-PadA)") (class "Default")
      (node (ref "AVR1") (pin "A") (pinfunction "A_A") (pintype "passive"))
      (node (ref "R5") (pin "1") (pinfunction "1_1") (pintype "passive"))
    )
    (net (code "75") (name "Net-(BUTTON-PadP$1)") (class "Default")
      (node (ref "BUTTON") (pin "P$1") (pinfunction "P$1_P$1") (pintype "bidirectional"))
      (node (ref "R31") (pin "2") (pinfunction "2_2") (pintype "passive"))
    )
    (net (code "76") (name "Net-(C21-Pad1)") (class "Default")
      (node (ref "C21") (pin "1") (pinfunction "1_1") (pintype "passive"))
      (node (ref "L5") (pin "2") (pinfunction "2_2") (pintype "passive"))
    )
    (net (code "77") (name "Net-(C21-Pad2)") (class "Default")
      (node (ref "C21") (pin "2") (pinfunction "2_2") (pintype "passive"))
      (node (ref "C22") (pin "1") (pinfunction "1_1") (pintype "passive"))
      (node (ref "C24") (pin "1") (pinfunction "1_1") (pintype "passive"))
      (node (ref "L6") (pin "2") (pinfunction "2_2") (pintype "passive"))
    )
    (net (code "78") (name "Net-(C22-Pad2)") (class "Default")
      (node (ref "C22") (pin "2") (pinfunction "2_2") (pintype "passive"))
      (node (ref "SMA") (pin "SIG") (pinfunction "SIG_SIG") (pintype "bidirectional"))
    )
    (net (code "79") (name "Net-(C23-Pad1)") (class "Default")
      (node (ref "C23") (pin "1") (pinfunction "1_1") (pintype "passive"))
      (node (ref "L4") (pin "2") (pinfunction "2_2") (pintype "passive"))
      (node (ref "L5") (pin "1") (pinfunction "1_1") (pintype "passive"))
    )
    (net (code "80") (name "Net-(C52-Pad1)") (class "Default")
      (node (ref "C52") (pin "1") (pinfunction "1_1") (pintype "passive"))
      (node (ref "R41") (pin "1") (pinfunction "1_1") (pintype "passive"))
    )
    (net (code "81") (name "Net-(C52-Pad2)") (class "Default")
      (node (ref "C52") (pin "2") (pinfunction "2_2") (pintype "passive"))
      (node (ref "C98") (pin "1") (pinfunction "1_1") (pintype "passive"))
      (node (ref "R9") (pin "2") (pinfunction "2_2") (pintype "passive"))
    )
    (net (code "82") (name "Net-(C54-Pad1)") (class "Default")
      (node (ref "C54") (pin "1") (pinfunction "1_1") (pintype "passive"))
      (node (ref "L17") (pin "1") (pinfunction "1_1") (pintype "passive"))
      (node (ref "TO_AUX1") (pin "1") (pinfunction "1_1") (pintype "bidirectional"))
      (node (ref "TO_AUX1") (pin "2") (pinfunction "2_2") (pintype "bidirectional"))
    )
    (net (code "83") (name "Net-(C62-Pad1)") (class "Default")
      (node (ref "C62") (pin "1") (pinfunction "1_1") (pintype "passive"))
      (node (ref "L19") (pin "1") (pinfunction "1_1") (pintype "passive"))
      (node (ref "TO_AUX2") (pin "2") (pinfunction "2_2") (pintype "bidirectional"))
      (node (ref "TO_AUX2") (pin "4") (pinfunction "4_4") (pintype "bidirectional"))
    )
    (net (code "84") (name "Net-(C67-Pad1)") (class "Default")
      (node (ref "C67") (pin "1") (pinfunction "1_1") (pintype "passive"))
      (node (ref "R40") (pin "1") (pinfunction "1_1") (pintype "passive"))
    )
    (net (code "85") (name "Net-(C67-Pad2)") (class "Default")
      (node (ref "C67") (pin "2") (pinfunction "2_2") (pintype "passive"))
      (node (ref "C99") (pin "1") (pinfunction "1_1") (pintype "passive"))
      (node (ref "R14") (pin "2") (pinfunction "2_2") (pintype "passive"))
    )
    (net (code "86") (name "Net-(CC1-PadC)") (class "Default")
      (node (ref "CC1") (pin "C") (pinfunction "C_C") (pintype "passive"))
      (node (ref "R4") (pin "2") (pinfunction "2_2") (pintype "passive"))
    )
    (net (code "87") (name "Net-(CHARGE-PadA)") (class "Default")
      (node (ref "CHARGE") (pin "A") (pinfunction "A_A") (pintype "passive"))
      (node (ref "R11") (pin "1") (pinfunction "1_1") (pintype "passive"))
    )
    (net (code "88") (name "Net-(NEXT-PadP$1)") (class "Default")
      (node (ref "NEXT") (pin "P$1") (pinfunction "P$1_P$1") (pintype "bidirectional"))
      (node (ref "R30") (pin "2") (pinfunction "2_2") (pintype "passive"))
    )
    (net (code "89") (name "Net-(PLAY/PAUSE-PadP$1)") (class "Default")
      (node (ref "PLAY/PAUSE") (pin "P$1") (pinfunction "P$1_P$1") (pintype "bidirectional"))
      (node (ref "R36") (pin "2") (pinfunction "2_2") (pintype "passive"))
    )
    (net (code "90") (name "Net-(POWER-PadA)") (class "Default")
      (node (ref "POWER") (pin "A") (pinfunction "A_A") (pintype "passive"))
      (node (ref "R12") (pin "1") (pinfunction "1_1") (pintype "passive"))
    )
    (net (code "91") (name "Net-(PREV-PadP$1)") (class "Default")
      (node (ref "PREV") (pin "P$1") (pinfunction "P$1_P$1") (pintype "bidirectional"))
      (node (ref "R35") (pin "2") (pinfunction "2_2") (pintype "passive"))
    )
    (net (code "92") (name "Net-(Q2-D)") (class "Default")
      (node (ref "LED_UL") (pin "1") (pinfunction "KR_1") (pintype "passive"))
      (node (ref "LED_UL") (pin "1-2") (pinfunction "KR_1-2") (pintype "passive"))
      (node (ref "LED_UR") (pin "1") (pinfunction "KR_1") (pintype "passive"))
      (node (ref "LED_UR") (pin "1-2") (pinfunction "KR_1-2") (pintype "passive"))
      (node (ref "Q2") (pin "3") (pinfunction "D_3") (pintype "passive"))
    )
    (net (code "93") (name "Net-(Q3-D)") (class "Default")
      (node (ref "LED_LL") (pin "1") (pinfunction "KR_1") (pintype "passive"))
      (node (ref "LED_LL") (pin "1-2") (pinfunction "KR_1-2") (pintype "passive"))
      (node (ref "LED_LR") (pin "1") (pinfunction "KR_1") (pintype "passive"))
      (node (ref "LED_LR") (pin "1-2") (pinfunction "KR_1-2") (pintype "passive"))
      (node (ref "Q3") (pin "3") (pinfunction "D_3") (pintype "passive"))
    )
    (net (code "94") (name "Net-(Q4-D)") (class "Default")
      (node (ref "LED_UL") (pin "4") (pinfunction "KG_4") (pintype "passive"))
      (node (ref "LED_UL") (pin "4-2") (pinfunction "KG_4-2") (pintype "passive"))
      (node (ref "LED_UR") (pin "4") (pinfunction "KG_4") (pintype "passive"))
      (node (ref "LED_UR") (pin "4-2") (pinfunction "KG_4-2") (pintype "passive"))
      (node (ref "Q4") (pin "3") (pinfunction "D_3") (pintype "passive"))
    )
    (net (code "95") (name "Net-(Q5-D)") (class "Default")
      (node (ref "LED_LL") (pin "4") (pinfunction "KG_4") (pintype "passive"))
      (node (ref "LED_LL") (pin "4-2") (pinfunction "KG_4-2") (pintype "passive"))
      (node (ref "LED_LR") (pin "4") (pinfunction "KG_4") (pintype "passive"))
      (node (ref "LED_LR") (pin "4-2") (pinfunction "KG_4-2") (pintype "passive"))
      (node (ref "Q5") (pin "3") (pinfunction "D_3") (pintype "passive"))
    )
    (net (code "96") (name "Net-(Q6-D)") (class "Default")
      (node (ref "LED_UL") (pin "3") (pinfunction "KB_3") (pintype "passive"))
      (node (ref "LED_UL") (pin "3-2") (pinfunction "KB_3-2") (pintype "passive"))
      (node (ref "LED_UR") (pin "3") (pinfunction "KB_3") (pintype "passive"))
      (node (ref "LED_UR") (pin "3-2") (pinfunction "KB_3-2") (pintype "passive"))
      (node (ref "Q6") (pin "3") (pinfunction "D_3") (pintype "passive"))
    )
    (net (code "97") (name "Net-(Q7-D)") (class "Default")
      (node (ref "LED_LL") (pin "3") (pinfunction "KB_3") (pintype "passive"))
      (node (ref "LED_LL") (pin "3-2") (pinfunction "KB_3-2") (pintype "passive"))
      (node (ref "LED_LR") (pin "3") (pinfunction "KB_3") (pintype "passive"))
      (node (ref "LED_LR") (pin "3-2") (pinfunction "KB_3-2") (pintype "passive"))
      (node (ref "Q7") (pin "3") (pinfunction "D_3") (pintype "passive"))
    )
    (net (code "98") (name "Net-(R29-Pad2)") (class "Default")
      (node (ref "R29") (pin "2") (pinfunction "2_2") (pintype "passive"))
      (node (ref "STOP") (pin "P$1") (pinfunction "P$1_P$1") (pintype "bidirectional"))
    )
    (net (code "99") (name "Net-(R32-Pad2)") (class "Default")
      (node (ref "R32") (pin "2") (pinfunction "2_2") (pintype "passive"))
      (node (ref "VOL+") (pin "P$1") (pinfunction "P$1_P$1") (pintype "bidirectional"))
    )
    (net (code "100") (name "Net-(R33-Pad2)") (class "Default")
      (node (ref "R33") (pin "2") (pinfunction "2_2") (pintype "passive"))
      (node (ref "WIRELESS") (pin "P$1") (pinfunction "P$1_P$1") (pintype "bidirectional"))
    )
    (net (code "101") (name "Net-(R34-Pad2)") (class "Default")
      (node (ref "R34") (pin "2") (pinfunction "2_2") (pintype "passive"))
      (node (ref "VOL-") (pin "P$1") (pinfunction "P$1_P$1") (pintype "bidirectional"))
    )
    (net (code "102") (name "Net-(U1-ANT)") (class "Default")
      (node (ref "L4") (pin "1") (pinfunction "1_1") (pintype "passive"))
      (node (ref "U1") (pin "11") (pinfunction "ANT_11") (pintype "bidirectional"))
    )
    (net (code "103") (name "Net-(U1-BIAS)") (class "Default")
      (node (ref "R2") (pin "2") (pinfunction "2_2") (pintype "passive"))
      (node (ref "U1") (pin "15") (pinfunction "BIAS_15") (pintype "bidirectional"))
    )
    (net (code "104") (name "Net-(U1-HGM)") (class "Default")
      (node (ref "R1") (pin "1") (pinfunction "1_1") (pintype "passive"))
      (node (ref "U1") (pin "7") (pinfunction "HGM_7") (pintype "bidirectional"))
    )
    (net (code "105") (name "Net-(U2-AD0{slash}GIO7)") (class "Default")
      (node (ref "L11") (pin "2") (pinfunction "2_2") (pintype "passive"))
      (node (ref "U2") (pin "16") (pinfunction "AD0/GIO7_16") (pintype "bidirectional"))
    )
    (net (code "106") (name "Net-(U2-AD1{slash}GIO8)") (class "Default")
      (node (ref "L13") (pin "2") (pinfunction "2_2") (pintype "passive"))
      (node (ref "U2") (pin "17") (pinfunction "AD1/GIO8_17") (pintype "bidirectional"))
    )
    (net (code "107") (name "Net-(U2-BCLK{slash}GIO5)") (class "Default")
      (node (ref "L9") (pin "2") (pinfunction "2_2") (pintype "passive"))
      (node (ref "U2") (pin "14") (pinfunction "BCLK/GIO5_14") (pintype "bidirectional"))
    )
    (net (code "108") (name "Net-(U2-DCPL)") (class "Default")
      (node (ref "C25") (pin "1") (pinfunction "1_1") (pintype "passive"))
      (node (ref "U2") (pin "39") (pinfunction "DCPL_39") (pintype "bidirectional"))
    )
    (net (code "109") (name "Net-(U2-GIO3)") (class "Default")
      (node (ref "R4") (pin "1") (pinfunction "1_1") (pintype "passive"))
      (node (ref "U2") (pin "9") (pinfunction "GIO3_9") (pintype "bidirectional"))
    )
    (net (code "110") (name "Net-(U2-MCLK{slash}GIO4)") (class "Default")
      (node (ref "L8") (pin "2") (pinfunction "2_2") (pintype "passive"))
      (node (ref "U2") (pin "13") (pinfunction "MCLK/GIO4_13") (pintype "bidirectional"))
    )
    (net (code "111") (name "Net-(U2-RBIAS)") (class "Default")
      (node (ref "R3") (pin "2") (pinfunction "2_2") (pintype "passive"))
      (node (ref "U2") (pin "30") (pinfunction "RBIAS_30") (pintype "bidirectional"))
    )
    (net (code "112") (name "Net-(U2-WCLK{slash}GIO6)") (class "Default")
      (node (ref "L10") (pin "2") (pinfunction "2_2") (pintype "passive"))
      (node (ref "U2") (pin "15") (pinfunction "WCLK/GIO6_15") (pintype "bidirectional"))
    )
    (net (code "113") (name "Net-(U2-X0)") (class "Default")
      (node (ref "C27") (pin "1") (pinfunction "1_1") (pintype "passive"))
      (node (ref "U2") (pin "22") (pinfunction "X0_22") (pintype "bidirectional"))
      (node (ref "X1") (pin "3") (pinfunction "2_3") (pintype "passive"))
    )
    (net (code "114") (name "Net-(U2-X1)") (class "Default")
      (node (ref "C26") (pin "1") (pinfunction "1_1") (pintype "passive"))
      (node (ref "U2") (pin "21") (pinfunction "X1_21") (pintype "bidirectional"))
      (node (ref "X1") (pin "1") (pinfunction "1_1") (pintype "passive"))
    )
    (net (code "115") (name "Net-(U2-XPAEN)") (class "Default")
      (node (ref "L12") (pin "1") (pinfunction "1_1") (pintype "passive"))
      (node (ref "U2") (pin "36") (pinfunction "XPAEN_36") (pintype "bidirectional"))
    )
    (net (code "116") (name "Net-(U2-~{RESET})") (class "Default")
      (node (ref "L7") (pin "1") (pinfunction "1_1") (pintype "passive"))
      (node (ref "U2") (pin "11") (pinfunction "~{RESET}_11") (pintype "bidirectional"))
    )
    (net (code "117") (name "Net-(U3-AINA)") (class "Default")
      (node (ref "C36") (pin "2") (pinfunction "2_2") (pintype "passive"))
      (node (ref "U3") (pin "15") (pinfunction "AINA_15") (pintype "bidirectional"))
    )
    (net (code "118") (name "Net-(U3-AINB)") (class "Default")
      (node (ref "C38") (pin "2") (pinfunction "2_2") (pintype "passive"))
      (node (ref "U3") (pin "16") (pinfunction "AINB_16") (pintype "bidirectional"))
    )
    (net (code "119") (name "Net-(U3-FILT+)") (class "Default")
      (node (ref "C44") (pin "1") (pinfunction "1_1") (pintype "passive"))
      (node (ref "C45") (pin "1") (pinfunction "1_1") (pintype "passive"))
      (node (ref "U3") (pin "18") (pinfunction "FILT+_18") (pintype "bidirectional"))
    )
    (net (code "120") (name "Net-(U3-VQ)") (class "Default")
      (node (ref "C46") (pin "1") (pinfunction "1_1") (pintype "passive"))
      (node (ref "C47") (pin "1") (pinfunction "1_1") (pintype "passive"))
      (node (ref "U3") (pin "17") (pinfunction "VQ_17") (pintype "bidirectional"))
    )
    (net (code "121") (name "Net-(U4-BYPASS)") (class "Default")
      (node (ref "C63") (pin "1") (pinfunction "1_1") (pintype "passive"))
      (node (ref "U4") (pin "1") (pinfunction "BYPASS_1") (pintype "bidirectional"))
    )
    (net (code "122") (name "Net-(U4-INA)") (class "Default")
      (node (ref "R7") (pin "2") (pinfunction "2_2") (pintype "passive"))
      (node (ref "R9") (pin "1") (pinfunction "1_1") (pintype "passive"))
      (node (ref "U4") (pin "8") (pinfunction "INA_8") (pintype "bidirectional"))
    )
    (net (code "123") (name "Net-(U4-INB)") (class "Default")
      (node (ref "R14") (pin "1") (pinfunction "1_1") (pintype "passive"))
      (node (ref "R21") (pin "2") (pinfunction "2_2") (pintype "passive"))
      (node (ref "U4") (pin "4") (pinfunction "INB_4") (pintype "bidirectional"))
    )
    (net (code "124") (name "Net-(U4-OUTB)") (class "Default")
      (node (ref "C66") (pin "1") (pinfunction "1_1") (pintype "passive"))
      (node (ref "R21") (pin "1") (pinfunction "1_1") (pintype "passive"))
      (node (ref "U4") (pin "5") (pinfunction "OUTB_5") (pintype "bidirectional"))
    )
    (net (code "125") (name "Net-(U4-SHUTDOWN)") (class "Default")
      (node (ref "R10") (pin "1") (pinfunction "1_1") (pintype "passive"))
      (node (ref "U4") (pin "3") (pinfunction "SHUTDOWN_3") (pintype "bidirectional"))
    )
    (net (code "126") (name "Net-(U5-VIN)") (class "Default")
      (node (ref "F1") (pin "2") (pinfunction "2_2") (pintype "passive"))
      (node (ref "L21") (pin "2") (pinfunction "2_2") (pintype "passive"))
      (node (ref "U5") (pin "1") (pinfunction "VIN_1") (pintype "bidirectional"))
    )
    (net (code "127") (name "Net-(U6-ISET)") (class "Default")
      (node (ref "R38") (pin "2") (pinfunction "2_2") (pintype "passive"))
      (node (ref "U6") (pin "2") (pinfunction "ISET_2") (pintype "bidirectional"))
    )
    (net (code "128") (name "Net-(U6-PRETERM)") (class "Default")
      (node (ref "R39") (pin "2") (pinfunction "2_2") (pintype "passive"))
      (node (ref "U6") (pin "4") (pinfunction "PRETERM_4") (pintype "bidirectional"))
    )
    (net (code "129") (name "Net-(U6-TS)") (class "Default")
      (node (ref "R37") (pin "2") (pinfunction "2_2") (pintype "passive"))
      (node (ref "U6") (pin "9") (pinfunction "TS_9") (pintype "bidirectional"))
    )
    (net (code "130") (name "Net-(U6-~{CHG})") (class "Default")
      (node (ref "CHARGE") (pin "C") (pinfunction "C_C") (pintype "passive"))
      (node (ref "U6") (pin "8") (pinfunction "~{CHG}_8") (pintype "bidirectional"))
    )
    (net (code "131") (name "Net-(U7-EN)") (class "Default")
      (node (ref "C71") (pin "1") (pinfunction "1_1") (pintype "passive"))
      (node (ref "L21") (pin "1") (pinfunction "1_1") (pintype "passive"))
      (node (ref "U7") (pin "1") (pinfunction "VIN_1") (pintype "bidirectional"))
      (node (ref "U7") (pin "3") (pinfunction "EN_3") (pintype "bidirectional"))
    )
    (net (code "132") (name "Net-(U9-FILTP)") (class "Default")
      (node (ref "C82") (pin "1") (pinfunction "1_1") (pintype "passive"))
      (node (ref "U9") (pin "6") (pinfunction "FILTP_6") (pintype "bidirectional"))
    )
    (net (code "133") (name "Net-(U10C-PC02)") (class "Default")
      (node (ref "C83") (pin "1") (pinfunction "1_1") (pintype "passive"))
      (node (ref "U10") (pin "18") (pinfunction "PC02_18") (pintype "bidirectional"))
      (node (ref "X2") (pin "X1") (pinfunction "1_X1") (pintype "passive"))
    )
    (net (code "134") (name "Net-(U10C-PC03)") (class "Default")
      (node (ref "C84") (pin "1") (pinfunction "1_1") (pintype "passive"))
      (node (ref "U10") (pin "19") (pinfunction "PC03_19") (pintype "bidirectional"))
      (node (ref "X2") (pin "X2") (pinfunction "2_X2") (pintype "passive"))
    )
    (net (code "135") (name "Net-(U10D-D+_FS)") (class "Default")
      (node (ref "R15") (pin "1") (pinfunction "1_1") (pintype "passive"))
      (node (ref "U10") (pin "9") (pinfunction "D+_FS_9") (pintype "bidirectional"))
    )
    (net (code "136") (name "Net-(U10D-D-_FS)") (class "Default")
      (node (ref "R17") (pin "1") (pinfunction "1_1") (pintype "passive"))
      (node (ref "U10") (pin "8") (pinfunction "D-_FS_8") (pintype "bidirectional"))
    )
    (net (code "137") (name "Net-(U10D-USB_VBIAS)") (class "Default")
      (node (ref "C76") (pin "1") (pinfunction "1_1") (pintype "passive"))
      (node (ref "R27") (pin "2") (pinfunction "2_2") (pintype "passive"))
      (node (ref "U10") (pin "3") (pinfunction "USB_VBIAS_3") (pintype "bidirectional"))
    )
    (net (code "138") (name "Net-(U10E-VDDCORE)") (class "Default")
      (node (ref "C68") (pin "1") (pinfunction "1_1") (pintype "passive"))
      (node (ref "C69") (pin "1") (pinfunction "1_1") (pintype "passive"))
      (node (ref "U10") (pin "141") (pinfunction "VDDCORE_141") (pintype "bidirectional"))
    )
    (net (code "139") (name "Net-(U10F-PX37)") (class "Default")
      (node (ref "U10") (pin "45") (pinfunction "PX37_45") (pintype "bidirectional"))
      (node (ref "U9") (pin "5") (pinfunction "CLK_IN_5") (pintype "bidirectional"))
    )
    (net (code "140") (name "Net-(U11-SNS0)") (class "Default")
      (node (ref "C87") (pin "1") (pinfunction "1_1") (pintype "passive"))
      (node (ref "U11") (pin "32") (pinfunction "SNS0_32") (pintype "bidirectional"))
    )
    (net (code "141") (name "Net-(U11-SNS0K)") (class "Default")
      (node (ref "C87") (pin "2") (pinfunction "2_2") (pintype "passive"))
      (node (ref "R29") (pin "1") (pinfunction "1_1") (pintype "passive"))
      (node (ref "U11") (pin "1") (pinfunction "SNS0K_1") (pintype "bidirectional"))
    )
    (net (code "142") (name "Net-(U11-SNS1)") (class "Default")
      (node (ref "C88") (pin "1") (pinfunction "1_1") (pintype "passive"))
      (node (ref "U11") (pin "2") (pinfunction "SNS1_2") (pintype "bidirectional"))
    )
    (net (code "143") (name "Net-(U11-SNS1K)") (class "Default")
      (node (ref "C88") (pin "2") (pinfunction "2_2") (pintype "passive"))
      (node (ref "R30") (pin "1") (pinfunction "1_1") (pintype "passive"))
      (node (ref "U11") (pin "3") (pinfunction "SNS1K_3") (pintype "bidirectional"))
    )
    (net (code "144") (name "Net-(U11-SNS2)") (class "Default")
      (node (ref "C89") (pin "1") (pinfunction "1_1") (pintype "passive"))
      (node (ref "U11") (pin "7") (pinfunction "SNS2_7") (pintype "bidirectional"))
    )
    (net (code "145") (name "Net-(U11-SNS2K)") (class "Default")
      (node (ref "C89") (pin "2") (pinfunction "2_2") (pintype "passive"))
      (node (ref "R31") (pin "1") (pinfunction "1_1") (pintype "passive"))
      (node (ref "U11") (pin "6") (pinfunction "SNS2K_6") (pintype "bidirectional"))
    )
    (net (code "146") (name "Net-(U11-SNS3)") (class "Default")
      (node (ref "C90") (pin "1") (pinfunction "1_1") (pintype "passive"))
      (node (ref "U11") (pin "8") (pinfunction "SNS3_8") (pintype "bidirectional"))
    )
    (net (code "147") (name "Net-(U11-SNS3K)") (class "Default")
      (node (ref "C90") (pin "2") (pinfunction "2_2") (pintype "passive"))
      (node (ref "R32") (pin "1") (pinfunction "1_1") (pintype "passive"))
      (node (ref "U11") (pin "9") (pinfunction "SNS3K_9") (pintype "bidirectional"))
    )
    (net (code "148") (name "Net-(U11-SNS4)") (class "Default")
      (node (ref "C91") (pin "1") (pinfunction "1_1") (pintype "passive"))
      (node (ref "U11") (pin "10") (pinfunction "SNS4_10") (pintype "bidirectional"))
    )
    (net (code "149") (name "Net-(U11-SNS4K)") (class "Default")
      (node (ref "C91") (pin "2") (pinfunction "2_2") (pintype "passive"))
      (node (ref "R33") (pin "1") (pinfunction "1_1") (pintype "passive"))
      (node (ref "U11") (pin "11") (pinfunction "SNS4K_11") (pintype "bidirectional"))
    )
    (net (code "150") (name "Net-(U11-SNS5)") (class "Default")
      (node (ref "C92") (pin "1") (pinfunction "1_1") (pintype "passive"))
      (node (ref "U11") (pin "12") (pinfunction "SNS5_12") (pintype "bidirectional"))
    )
    (net (code "151") (name "Net-(U11-SNS5K)") (class "Default")
      (node (ref "C92") (pin "2") (pinfunction "2_2") (pintype "passive"))
      (node (ref "R34") (pin "1") (pinfunction "1_1") (pintype "passive"))
      (node (ref "U11") (pin "13") (pinfunction "SNS5K_13") (pintype "bidirectional"))
    )
    (net (code "152") (name "Net-(U11-SNS6)") (class "Default")
      (node (ref "C93") (pin "1") (pinfunction "1_1") (pintype "passive"))
      (node (ref "U11") (pin "20") (pinfunction "SNS6_20") (pintype "bidirectional"))
    )
    (net (code "153") (name "Net-(U11-SNS6K)") (class "Default")
      (node (ref "C93") (pin "2") (pinfunction "2_2") (pintype "passive"))
      (node (ref "R35") (pin "1") (pinfunction "1_1") (pintype "passive"))
      (node (ref "U11") (pin "19") (pinfunction "SNS6K_19") (pintype "bidirectional"))
    )
    (net (code "154") (name "Net-(U11-SNS7K{slash}DETECT0)") (class "Default")
      (node (ref "C94") (pin "2") (pinfunction "2_2") (pintype "passive"))
      (node (ref "R36") (pin "1") (pinfunction "1_1") (pintype "passive"))
      (node (ref "U11") (pin "22") (pinfunction "SNS7K/DETECT0_22") (pintype "bidirectional"))
    )
    (net (code "155") (name "Net-(U11-SNS7{slash}DETECT1)") (class "Default")
      (node (ref "C94") (pin "1") (pinfunction "1_1") (pintype "passive"))
      (node (ref "U11") (pin "23") (pinfunction "SNS7/DETECT1_23") (pintype "bidirectional"))
    )
    (net (code "156") (name "Net-(U11-~{RESET})") (class "Default")
      (node (ref "R28") (pin "1") (pinfunction "1_1") (pintype "passive"))
      (node (ref "U11") (pin "29") (pinfunction "~{RESET}_29") (pintype "bidirectional"))
    )
    (net (code "157") (name "OUT_L") (class "Default")
      (node (ref "R41") (pin "2") (pinfunction "2_2") (pintype "passive"))
      (node (ref "U3") (pin "23") (pinfunction "OUTB_23") (pintype "bidirectional"))
    )
    (net (code "158") (name "OUT_R") (class "Default")
      (node (ref "R40") (pin "2") (pinfunction "2_2") (pintype "passive"))
      (node (ref "U3") (pin "22") (pinfunction "OUTA_22") (pintype "bidirectional"))
    )
    (net (code "159") (name "PA_EN") (class "Default")
      (node (ref "L12") (pin "2") (pinfunction "2_2") (pintype "passive"))
      (node (ref "R6") (pin "2") (pinfunction "2_2") (pintype "passive"))
      (node (ref "U1") (pin "5") (pinfunction "PAEN_5") (pintype "bidirectional"))
    )
    (net (code "160") (name "PHONE_L") (class "Default")
      (node (ref "C53") (pin "2") (pinfunction "2_2") (pintype "passive"))
      (node (ref "PHONE_OUT") (pin "4") (pinfunction "L_4") (pintype "bidirectional"))
      (node (ref "R25") (pin "2") (pinfunction "2_2") (pintype "passive"))
    )
    (net (code "161") (name "PHONE_R") (class "Default")
      (node (ref "C66") (pin "2") (pinfunction "2_2") (pintype "passive"))
      (node (ref "PHONE_OUT") (pin "1") (pinfunction "R_1") (pintype "bidirectional"))
    )
    (net (code "162") (name "PHONE_SENSE") (class "Default")
      (node (ref "PHONE_OUT") (pin "3") (pinfunction "L_SW_3") (pintype "bidirectional"))
      (node (ref "R16") (pin "1") (pinfunction "1_1") (pintype "passive"))
      (node (ref "U10") (pin "115") (pinfunction "PA18_115") (pintype "bidirectional"))
    )
    (net (code "163") (name "RED_BOT") (class "Default")
      (node (ref "TO_AUX1") (pin "4") (pinfunction "4_4") (pintype "bidirectional"))
      (node (ref "U10") (pin "132") (pinfunction "PA12_132") (pintype "bidirectional"))
    )
    (net (code "164") (name "RED_TOP") (class "Default")
      (node (ref "TO_AUX1") (pin "7") (pinfunction "7_7") (pintype "bidirectional"))
      (node (ref "U10") (pin "83") (pinfunction "PX17_83") (pintype "bidirectional"))
    )
    (net (code "165") (name "RF_N") (class "Default")
      (node (ref "U1") (pin "2") (pinfunction "RF_N_2") (pintype "bidirectional"))
      (node (ref "U2") (pin "25") (pinfunction "RF_N_25") (pintype "bidirectional"))
    )
    (net (code "166") (name "RF_P") (class "Default")
      (node (ref "U1") (pin "4") (pinfunction "RF_P_4") (pintype "bidirectional"))
      (node (ref "U2") (pin "24") (pinfunction "RF_P_24") (pintype "bidirectional"))
    )
    (net (code "167") (name "RTS") (class "Default")
      (node (ref "SERIAL") (pin "1") (pinfunction "1_1") (pintype "bidirectional"))
      (node (ref "U10") (pin "63") (pinfunction "PX03_63") (pintype "bidirectional"))
    )
    (net (code "168") (name "RXD") (class "Default")
      (node (ref "SERIAL") (pin "3") (pinfunction "3_3") (pintype "bidirectional"))
      (node (ref "U10") (pin "55") (pinfunction "PX00_55") (pintype "bidirectional"))
    )
    (net (code "169") (name "SCLK0") (class "Default")
      (node (ref "CC_DEBUG") (pin "6") (pinfunction "6_6") (pintype "bidirectional"))
      (node (ref "U10") (pin "137") (pinfunction "PA08_137") (pintype "bidirectional"))
      (node (ref "U2") (pin "4") (pinfunction "SCLK_4") (pintype "bidirectional"))
      (node (ref "U3") (pin "10") (pinfunction "SCL/SCLK_10") (pintype "bidirectional"))
      (node (ref "U9") (pin "9") (pinfunction "SCL/SCLK_9") (pintype "bidirectional"))
    )
    (net (code "170") (name "SCLK1") (class "Default")
      (node (ref "TO_AUX2") (pin "1") (pinfunction "1_1") (pintype "bidirectional"))
      (node (ref "U10") (pin "135") (pinfunction "PB07_135") (pintype "bidirectional"))
    )
    (net (code "171") (name "TCK") (class "Default")
      (node (ref "JTAG") (pin "1") (pinfunction "1_1") (pintype "bidirectional"))
      (node (ref "U10") (pin "107") (pinfunction "TCK_107") (pintype "bidirectional"))
    )
    (net (code "172") (name "TDI") (class "Default")
      (node (ref "JTAG") (pin "9") (pinfunction "9_9") (pintype "bidirectional"))
      (node (ref "U10") (pin "108") (pinfunction "TDI_108") (pintype "bidirectional"))
    )
    (net (code "173") (name "TDO") (class "Default")
      (node (ref "JTAG") (pin "3") (pinfunction "3_3") (pintype "bidirectional"))
      (node (ref "U10") (pin "105") (pinfunction "TDO_105") (pintype "bidirectional"))
    )
    (net (code "174") (name "TMS") (class "Default")
      (node (ref "JTAG") (pin "5") (pinfunction "5_5") (pintype "bidirectional"))
      (node (ref "U10") (pin "104") (pinfunction "TMS_104") (pintype "bidirectional"))
    )
    (net (code "175") (name "TXD") (class "Default")
      (node (ref "SERIAL") (pin "2") (pinfunction "2_2") (pintype "bidirectional"))
      (node (ref "U10") (pin "59") (pinfunction "PX01_59") (pintype "bidirectional"))
    )
    (net (code "176") (name "UC_MCLK") (class "Default")
      (node (ref "U10") (pin "13") (pinfunction "PC04_13") (pintype "bidirectional"))
      (node (ref "U8") (pin "1") (pinfunction "D_1") (pintype "bidirectional"))
      (node (ref "U8") (pin "4") (pinfunction "~{Q}_4") (pintype "bidirectional"))
    )
    (net (code "177") (name "USBOTGID") (class "Default")
      (node (ref "U10") (pin "121") (pinfunction "PB05_121") (pintype "bidirectional"))
      (node (ref "USB") (pin "4") (pinfunction "ID_4") (pintype "bidirectional"))
    )
    (net (code "178") (name "WCLK") (class "Default")
      (node (ref "L10") (pin "1") (pinfunction "1_1") (pintype "passive"))
      (node (ref "U10") (pin "44") (pinfunction "PX36_44") (pintype "bidirectional"))
      (node (ref "U10") (pin "89") (pinfunction "PX27_89") (pintype "bidirectional"))
      (node (ref "U10") (pin "90") (pinfunction "PX26_90") (pintype "bidirectional"))
      (node (ref "U3") (pin "2") (pinfunction "WCLK_2") (pintype "bidirectional"))
    )
    (net (code "179") (name "unconnected-(CC_DEBUG-Pad3)") (class "Default")
      (node (ref "CC_DEBUG") (pin "3") (pinfunction "3_3") (pintype "bidirectional"))
    )
    (net (code "180") (name "unconnected-(CC_DEBUG-Pad4)") (class "Default")
      (node (ref "CC_DEBUG") (pin "4") (pinfunction "4_4") (pintype "bidirectional"))
    )
    (net (code "181") (name "unconnected-(CC_DEBUG-Pad9)") (class "Default")
      (node (ref "CC_DEBUG") (pin "9") (pinfunction "9_9") (pintype "bidirectional"))
    )
    (net (code "182") (name "unconnected-(GPIO-Pad1)") (class "Default")
      (node (ref "GPIO") (pin "1") (pinfunction "1_1") (pintype "bidirectional"))
    )
    (net (code "183") (name "unconnected-(GPIO-Pad3)") (class "Default")
      (node (ref "GPIO") (pin "3") (pinfunction "3_3") (pintype "bidirectional"))
    )
    (net (code "184") (name "unconnected-(JTAG-Pad7)") (class "Default")
      (node (ref "JTAG") (pin "7") (pinfunction "7_7") (pintype "bidirectional"))
    )
    (net (code "185") (name "unconnected-(JTAG-Pad8)") (class "Default")
      (node (ref "JTAG") (pin "8") (pinfunction "8_8") (pintype "bidirectional"))
    )
    (net (code "186") (name "unconnected-(LINE_IN-R_SW-Pad2)") (class "Default")
      (node (ref "LINE_IN") (pin "2") (pinfunction "R_SW_2") (pintype "bidirectional"))
    )
    (net (code "187") (name "unconnected-(PHONE_OUT-R_SW-Pad2)") (class "Default")
      (node (ref "PHONE_OUT") (pin "2") (pinfunction "R_SW_2") (pintype "bidirectional"))
    )
    (net (code "188") (name "unconnected-(RESET-Pad2)") (class "Default")
      (node (ref "RESET") (pin "2") (pinfunction "2_2") (pintype "bidirectional"))
    )
    (net (code "189") (name "unconnected-(RESET-Pad4)") (class "Default")
      (node (ref "RESET") (pin "4") (pinfunction "4_4") (pintype "bidirectional"))
    )
    (net (code "190") (name "unconnected-(SERIAL-Pad4)") (class "Default")
      (node (ref "SERIAL") (pin "4") (pinfunction "4_4") (pintype "bidirectional"))
    )
    (net (code "191") (name "unconnected-(U1-RXTX-Pad3)") (class "Default")
      (node (ref "U1") (pin "3") (pinfunction "RXTX_3") (pintype "bidirectional"))
    )
    (net (code "192") (name "unconnected-(U2-GIO2-Pad8)") (class "Default")
      (node (ref "U2") (pin "8") (pinfunction "GIO2_8") (pintype "bidirectional"))
    )
    (net (code "193") (name "unconnected-(U2-USBN{slash}XANTN-Pad1)") (class "Default")
      (node (ref "U2") (pin "1") (pinfunction "USBN/XANTN_1") (pintype "bidirectional"))
    )
    (net (code "194") (name "unconnected-(U2-USBP{slash}XANTP-Pad2)") (class "Default")
      (node (ref "U2") (pin "2") (pinfunction "USBP/XANTP_2") (pintype "bidirectional"))
    )
    (net (code "195") (name "unconnected-(U3-AD2-Pad13)") (class "Default")
      (node (ref "U3") (pin "13") (pinfunction "AD2_13") (pintype "bidirectional"))
    )
    (net (code "196") (name "unconnected-(U6-~{PG}-Pad5)") (class "Default")
      (node (ref "U6") (pin "5") (pinfunction "~{PG}_5") (pintype "bidirectional"))
    )
    (net (code "197") (name "unconnected-(U9-AUX_OUT-Pad4)") (class "Default")
      (node (ref "U9") (pin "4") (pinfunction "AUX_OUT_4") (pintype "bidirectional"))
    )
    (net (code "198") (name "unconnected-(U10A-PA00-Pad122)") (class "Default")
      (node (ref "U10") (pin "122") (pinfunction "PA00_122") (pintype "bidirectional"))
    )
    (net (code "199") (name "unconnected-(U10A-PA01-Pad123)") (class "Default")
      (node (ref "U10") (pin "123") (pinfunction "PA01_123") (pintype "bidirectional"))
    )
    (net (code "200") (name "unconnected-(U10A-PA02-Pad15)") (class "Default")
      (node (ref "U10") (pin "15") (pinfunction "PA02_15") (pintype "bidirectional"))
    )
    (net (code "201") (name "unconnected-(U10A-PA05-Pad124)") (class "Default")
      (node (ref "U10") (pin "124") (pinfunction "PA05_124") (pintype "bidirectional"))
    )
    (net (code "202") (name "unconnected-(U10A-PA15-Pad101)") (class "Default")
      (node (ref "U10") (pin "101") (pinfunction "PA15_101") (pintype "bidirectional"))
    )
    (net (code "203") (name "unconnected-(U10A-PA16-Pad128)") (class "Default")
      (node (ref "U10") (pin "128") (pinfunction "PA16_128") (pintype "bidirectional"))
    )
    (net (code "204") (name "unconnected-(U10A-PA20-Pad113)") (class "Default")
      (node (ref "U10") (pin "113") (pinfunction "PA20_113") (pintype "bidirectional"))
    )
    (net (code "205") (name "unconnected-(U10A-PA21-Pad109)") (class "Default")
      (node (ref "U10") (pin "109") (pinfunction "PA21_109") (pintype "bidirectional"))
    )
    (net (code "206") (name "unconnected-(U10A-PA22-Pad110)") (class "Default")
      (node (ref "U10") (pin "110") (pinfunction "PA22_110") (pintype "bidirectional"))
    )
    (net (code "207") (name "unconnected-(U10A-PA25-Pad119)") (class "Default")
      (node (ref "U10") (pin "119") (pinfunction "PA25_119") (pintype "bidirectional"))
    )
    (net (code "208") (name "unconnected-(U10A-PA26-Pad120)") (class "Default")
      (node (ref "U10") (pin "120") (pinfunction "PA26_120") (pintype "bidirectional"))
    )
    (net (code "209") (name "unconnected-(U10B-PB02-Pad25)") (class "Default")
      (node (ref "U10") (pin "25") (pinfunction "PB02_25") (pintype "bidirectional"))
    )
    (net (code "210") (name "unconnected-(U10B-PB03-Pad24)") (class "Default")
      (node (ref "U10") (pin "24") (pinfunction "PB03_24") (pintype "bidirectional"))
    )
    (net (code "211") (name "unconnected-(U10B-PB04-Pad22)") (class "Default")
      (node (ref "U10") (pin "22") (pinfunction "PB04_22") (pintype "bidirectional"))
    )
    (net (code "212") (name "unconnected-(U10B-PB06-Pad134)") (class "Default")
      (node (ref "U10") (pin "134") (pinfunction "PB06_134") (pintype "bidirectional"))
    )
    (net (code "213") (name "unconnected-(U10B-PB09-Pad17)") (class "Default")
      (node (ref "U10") (pin "17") (pinfunction "PB09_17") (pintype "bidirectional"))
    )
    (net (code "214") (name "unconnected-(U10B-PB11-Pad31)") (class "Default")
      (node (ref "U10") (pin "31") (pinfunction "PB11_31") (pintype "bidirectional"))
    )
    (net (code "215") (name "unconnected-(U10C-PC00-Pad98)") (class "Default")
      (node (ref "U10") (pin "98") (pinfunction "PC00_98") (pintype "bidirectional"))
    )
    (net (code "216") (name "unconnected-(U10C-PC01-Pad99)") (class "Default")
      (node (ref "U10") (pin "99") (pinfunction "PC01_99") (pintype "bidirectional"))
    )
    (net (code "217") (name "unconnected-(U10C-PC05-Pad12)") (class "Default")
      (node (ref "U10") (pin "12") (pinfunction "PC05_12") (pintype "bidirectional"))
    )
    (net (code "218") (name "unconnected-(U10F-PX04-Pad60)") (class "Default")
      (node (ref "U10") (pin "60") (pinfunction "PX04_60") (pintype "bidirectional"))
    )
    (net (code "219") (name "unconnected-(U10F-PX05-Pad58)") (class "Default")
      (node (ref "U10") (pin "58") (pinfunction "PX05_58") (pintype "bidirectional"))
    )
    (net (code "220") (name "unconnected-(U10F-PX06-Pad53)") (class "Default")
      (node (ref "U10") (pin "53") (pinfunction "PX06_53") (pintype "bidirectional"))
    )
    (net (code "221") (name "unconnected-(U10F-PX07-Pad54)") (class "Default")
      (node (ref "U10") (pin "54") (pinfunction "PX07_54") (pintype "bidirectional"))
    )
    (net (code "222") (name "unconnected-(U10F-PX09-Pad49)") (class "Default")
      (node (ref "U10") (pin "49") (pinfunction "PX09_49") (pintype "bidirectional"))
    )
    (net (code "223") (name "unconnected-(U10F-PX10-Pad37)") (class "Default")
      (node (ref "U10") (pin "37") (pinfunction "PX10_37") (pintype "bidirectional"))
    )
    (net (code "224") (name "unconnected-(U10F-PX11-Pad67)") (class "Default")
      (node (ref "U10") (pin "67") (pinfunction "PX11_67") (pintype "bidirectional"))
    )
    (net (code "225") (name "unconnected-(U10F-PX13-Pad33)") (class "Default")
      (node (ref "U10") (pin "33") (pinfunction "PX13_33") (pintype "bidirectional"))
    )
    (net (code "226") (name "unconnected-(U10F-PX16-Pad32)") (class "Default")
      (node (ref "U10") (pin "32") (pinfunction "PX16_32") (pintype "bidirectional"))
    )
    (net (code "227") (name "unconnected-(U10F-PX19-Pad35)") (class "Default")
      (node (ref "U10") (pin "35") (pinfunction "PX19_35") (pintype "bidirectional"))
    )
    (net (code "228") (name "unconnected-(U10F-PX20-Pad73)") (class "Default")
      (node (ref "U10") (pin "73") (pinfunction "PX20_73") (pintype "bidirectional"))
    )
    (net (code "229") (name "unconnected-(U10F-PX21-Pad80)") (class "Default")
      (node (ref "U10") (pin "80") (pinfunction "PX21_80") (pintype "bidirectional"))
    )
    (net (code "230") (name "unconnected-(U10F-PX22-Pad72)") (class "Default")
      (node (ref "U10") (pin "72") (pinfunction "PX22_72") (pintype "bidirectional"))
    )
    (net (code "231") (name "unconnected-(U10F-PX29-Pad94)") (class "Default")
      (node (ref "U10") (pin "94") (pinfunction "PX29_94") (pintype "bidirectional"))
    )
    (net (code "232") (name "unconnected-(U10F-PX35-Pad38)") (class "Default")
      (node (ref "U10") (pin "38") (pinfunction "PX35_38") (pintype "bidirectional"))
    )
    (net (code "233") (name "unconnected-(U10F-PX39-Pad52)") (class "Default")
      (node (ref "U10") (pin "52") (pinfunction "PX39_52") (pintype "bidirectional"))
    )
    (net (code "234") (name "unconnected-(U10F-PX40-Pad36)") (class "Default")
      (node (ref "U10") (pin "36") (pinfunction "PX40_36") (pintype "bidirectional"))
    )
    (net (code "235") (name "unconnected-(U10F-PX41-Pad71)") (class "Default")
      (node (ref "U10") (pin "71") (pinfunction "PX41_71") (pintype "bidirectional"))
    )
    (net (code "236") (name "unconnected-(U10F-PX42-Pad69)") (class "Default")
      (node (ref "U10") (pin "69") (pinfunction "PX42_69") (pintype "bidirectional"))
    )
    (net (code "237") (name "unconnected-(U10F-PX43-Pad88)") (class "Default")
      (node (ref "U10") (pin "88") (pinfunction "PX43_88") (pintype "bidirectional"))
    )
    (net (code "238") (name "unconnected-(U10F-PX44-Pad66)") (class "Default")
      (node (ref "U10") (pin "66") (pinfunction "PX44_66") (pintype "bidirectional"))
    )
    (net (code "239") (name "unconnected-(U10F-PX45-Pad70)") (class "Default")
      (node (ref "U10") (pin "70") (pinfunction "PX45_70") (pintype "bidirectional"))
    )
    (net (code "240") (name "unconnected-(U10F-PX47-Pad39)") (class "Default")
      (node (ref "U10") (pin "39") (pinfunction "PX47_39") (pintype "bidirectional"))
    )
    (net (code "241") (name "unconnected-(U10F-PX48-Pad41)") (class "Default")
      (node (ref "U10") (pin "41") (pinfunction "PX48_41") (pintype "bidirectional"))
    )
    (net (code "242") (name "unconnected-(U10F-PX49-Pad43)") (class "Default")
      (node (ref "U10") (pin "43") (pinfunction "PX49_43") (pintype "bidirectional"))
    )
    (net (code "243") (name "unconnected-(U10F-PX51-Pad77)") (class "Default")
      (node (ref "U10") (pin "77") (pinfunction "PX51_77") (pintype "bidirectional"))
    )
    (net (code "244") (name "unconnected-(U10F-PX52-Pad87)") (class "Default")
      (node (ref "U10") (pin "87") (pinfunction "PX52_87") (pintype "bidirectional"))
    )
    (net (code "245") (name "unconnected-(U10F-PX53-Pad42)") (class "Default")
      (node (ref "U10") (pin "42") (pinfunction "PX53_42") (pintype "bidirectional"))
    )
    (net (code "246") (name "unconnected-(U10F-PX54-Pad46)") (class "Default")
      (node (ref "U10") (pin "46") (pinfunction "PX54_46") (pintype "bidirectional"))
    )
    (net (code "247") (name "unconnected-(U10F-PX55-Pad79)") (class "Default")
      (node (ref "U10") (pin "79") (pinfunction "PX55_79") (pintype "bidirectional"))
    )
    (net (code "248") (name "unconnected-(U10F-PX56-Pad78)") (class "Default")
      (node (ref "U10") (pin "78") (pinfunction "PX56_78") (pintype "bidirectional"))
    )
    (net (code "249") (name "unconnected-(U10F-PX57-Pad76)") (class "Default")
      (node (ref "U10") (pin "76") (pinfunction "PX57_76") (pintype "bidirectional"))
    )
    (net (code "250") (name "unconnected-(U10F-PX58-Pad57)") (class "Default")
      (node (ref "U10") (pin "57") (pinfunction "PX58_57") (pintype "bidirectional"))
    )
    (net (code "251") (name "unconnected-(U10F-PX59-Pad56)") (class "Default")
      (node (ref "U10") (pin "56") (pinfunction "PX59_56") (pintype "bidirectional"))
    )
    (net (code "252") (name "unconnected-(U11-SNS8K{slash}DETECT3-Pad25)") (class "Default")
      (node (ref "U11") (pin "25") (pinfunction "SNS8K/DETECT3_25") (pintype "bidirectional"))
    )
    (net (code "253") (name "unconnected-(U11-SNS8{slash}DETECT2-Pad24)") (class "Default")
      (node (ref "U11") (pin "24") (pinfunction "SNS8/DETECT2_24") (pintype "bidirectional"))
    )
    (net (code "254") (name "unconnected-(U11-SNS9K{slash}DETECT5-Pad27)") (class "Default")
      (node (ref "U11") (pin "27") (pinfunction "SNS9K/DETECT5_27") (pintype "bidirectional"))
    )
    (net (code "255") (name "unconnected-(U11-SNS9{slash}DETECT4-Pad26)") (class "Default")
      (node (ref "U11") (pin "26") (pinfunction "SNS9/DETECT4_26") (pintype "bidirectional"))
    )
    (net (code "256") (name "unconnected-(U11-SNS10K{slash}SYNC-Pad31)") (class "Default")
      (node (ref "U11") (pin "31") (pinfunction "SNS10K/SYNC_31") (pintype "bidirectional"))
    )
    (net (code "257") (name "unconnected-(U11-SNS10{slash}DETECT16-Pad30)") (class "Default")
      (node (ref "U11") (pin "30") (pinfunction "SNS10/DETECT16_30") (pintype "bidirectional"))
    )
  )
)
